# Tello_Power_PCB.net
KiCad netlist of a schematic drawn in EAGLE
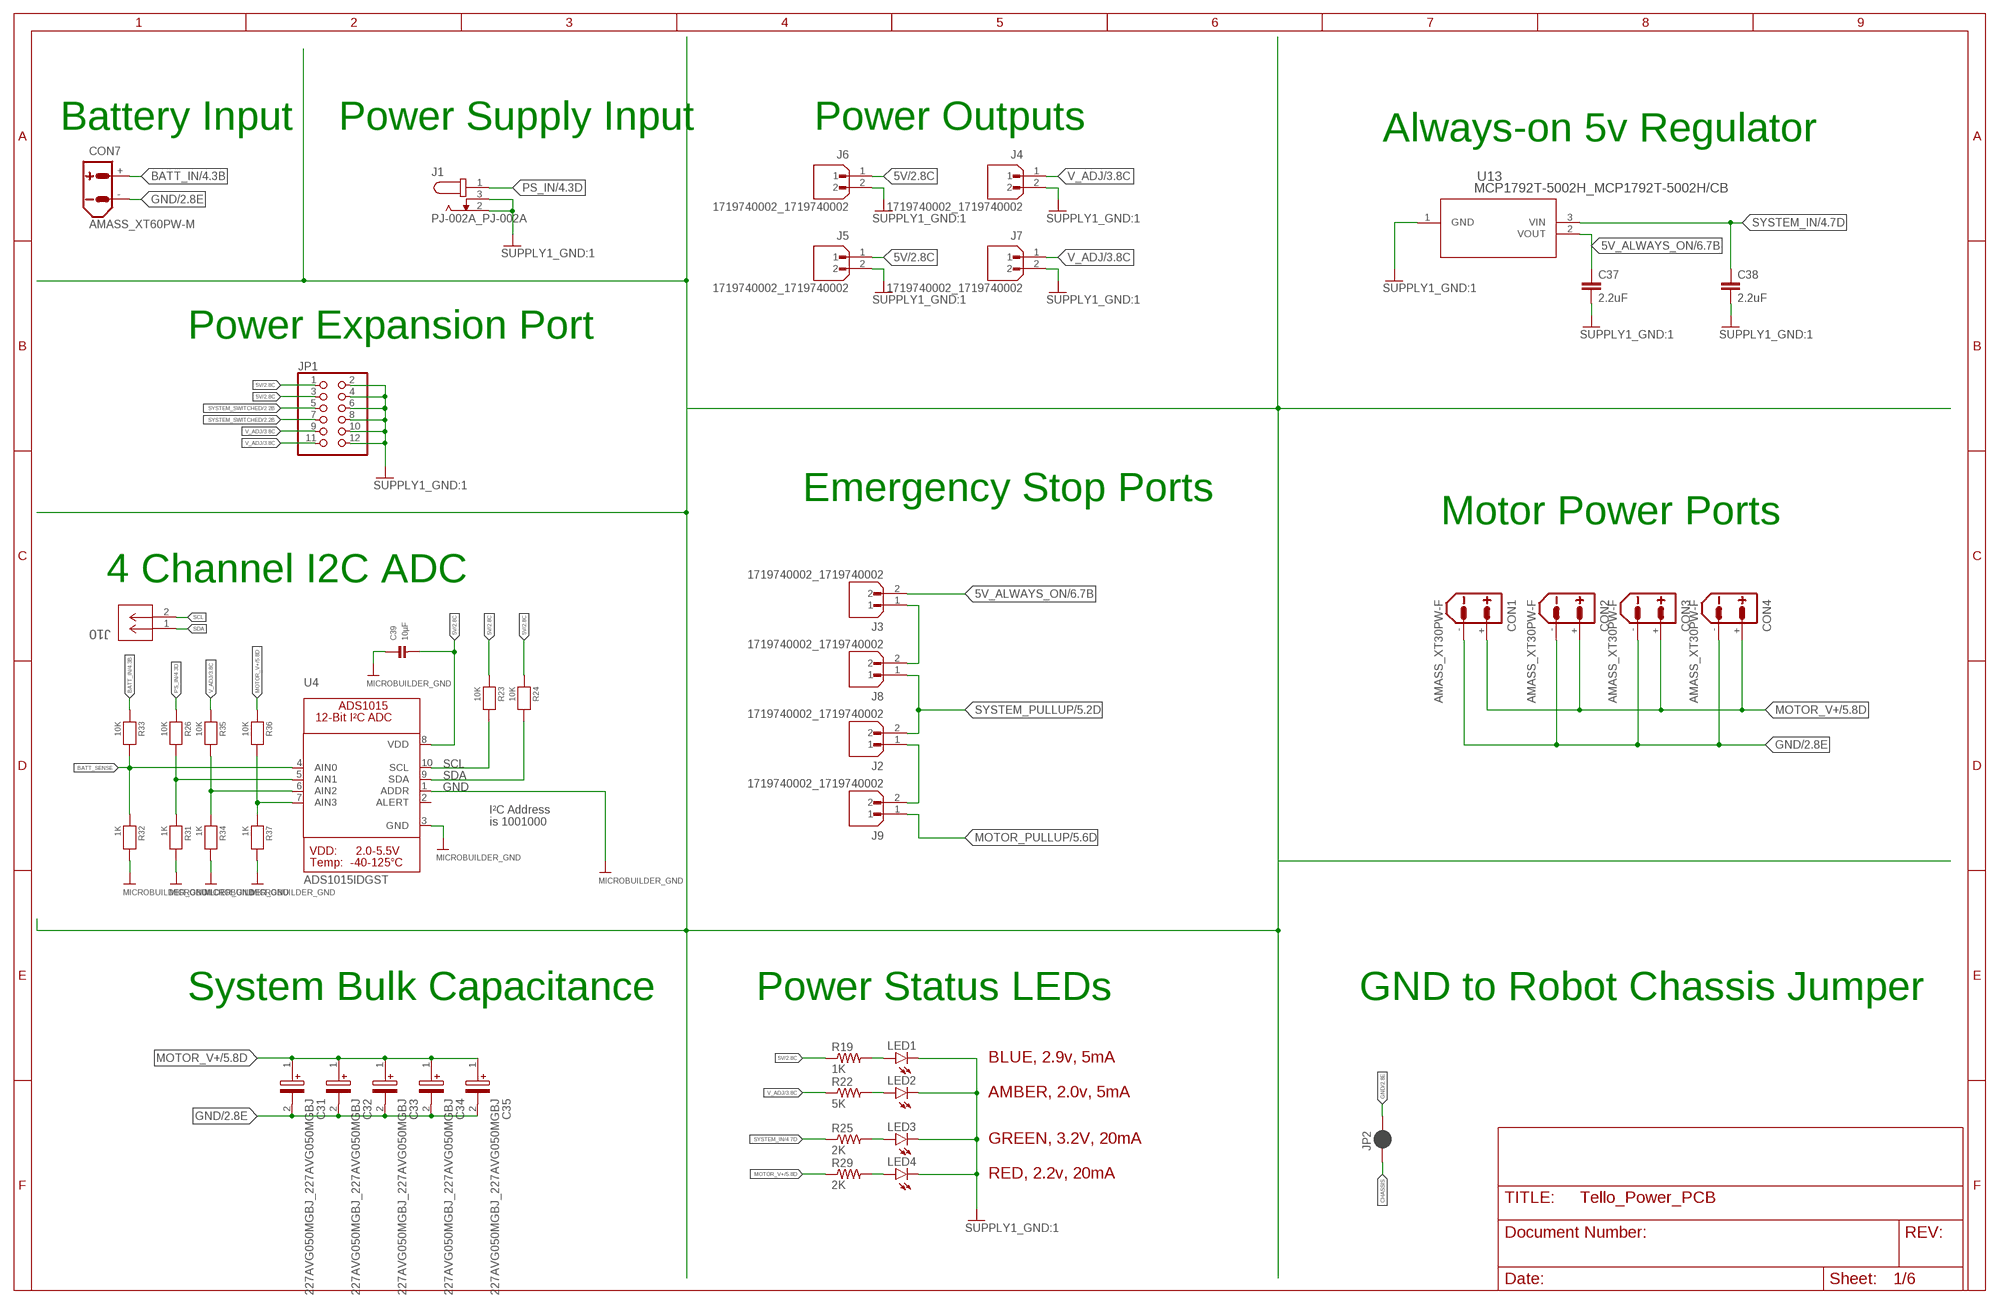
[diagram p0: schematic, sheet 1]
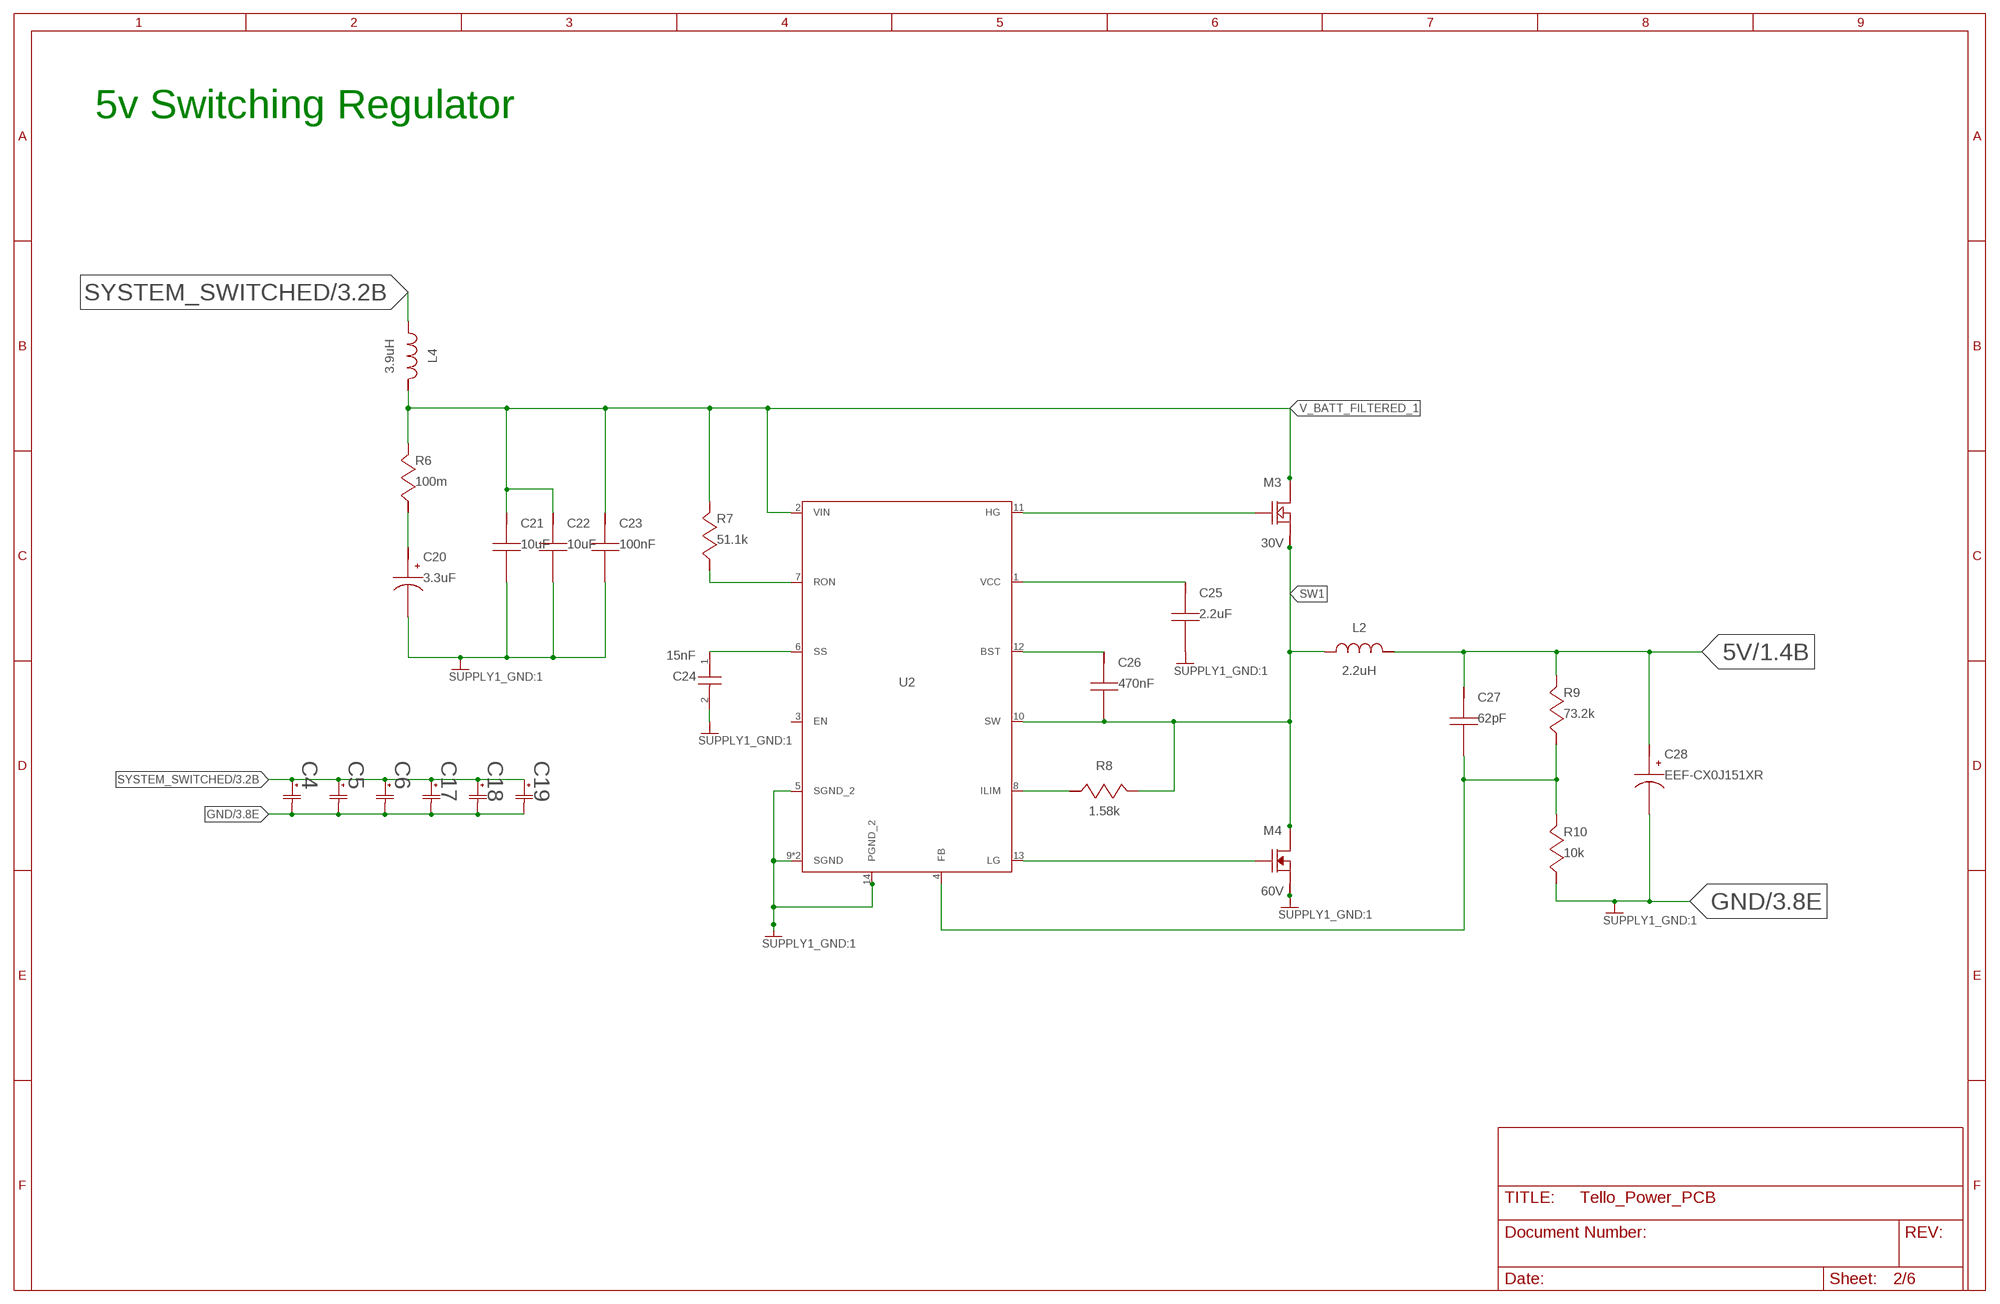
[diagram p1: schematic, sheet 2]
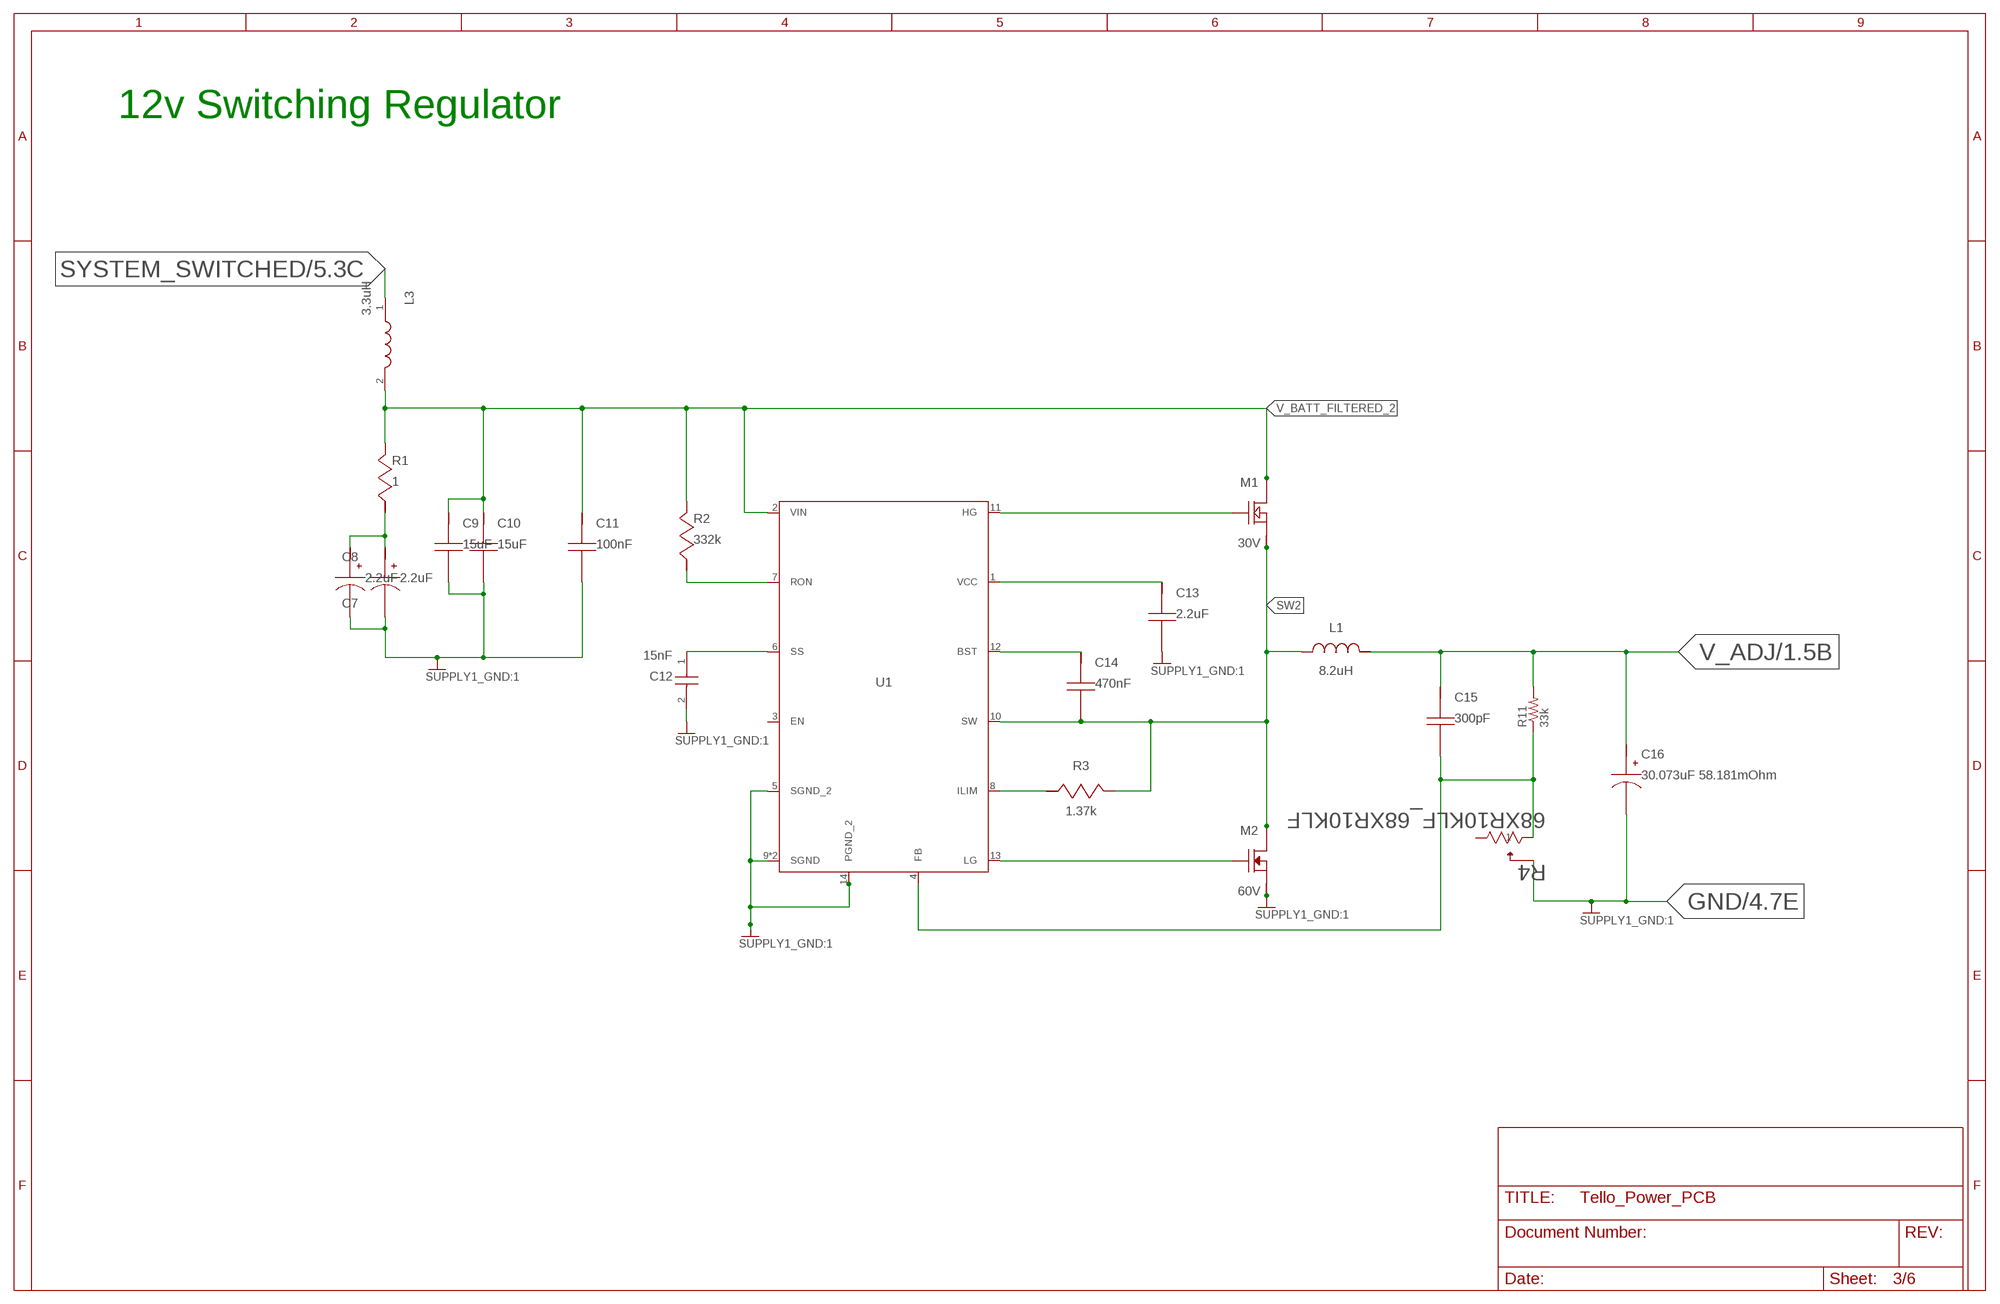
[diagram p2: schematic, sheet 3]
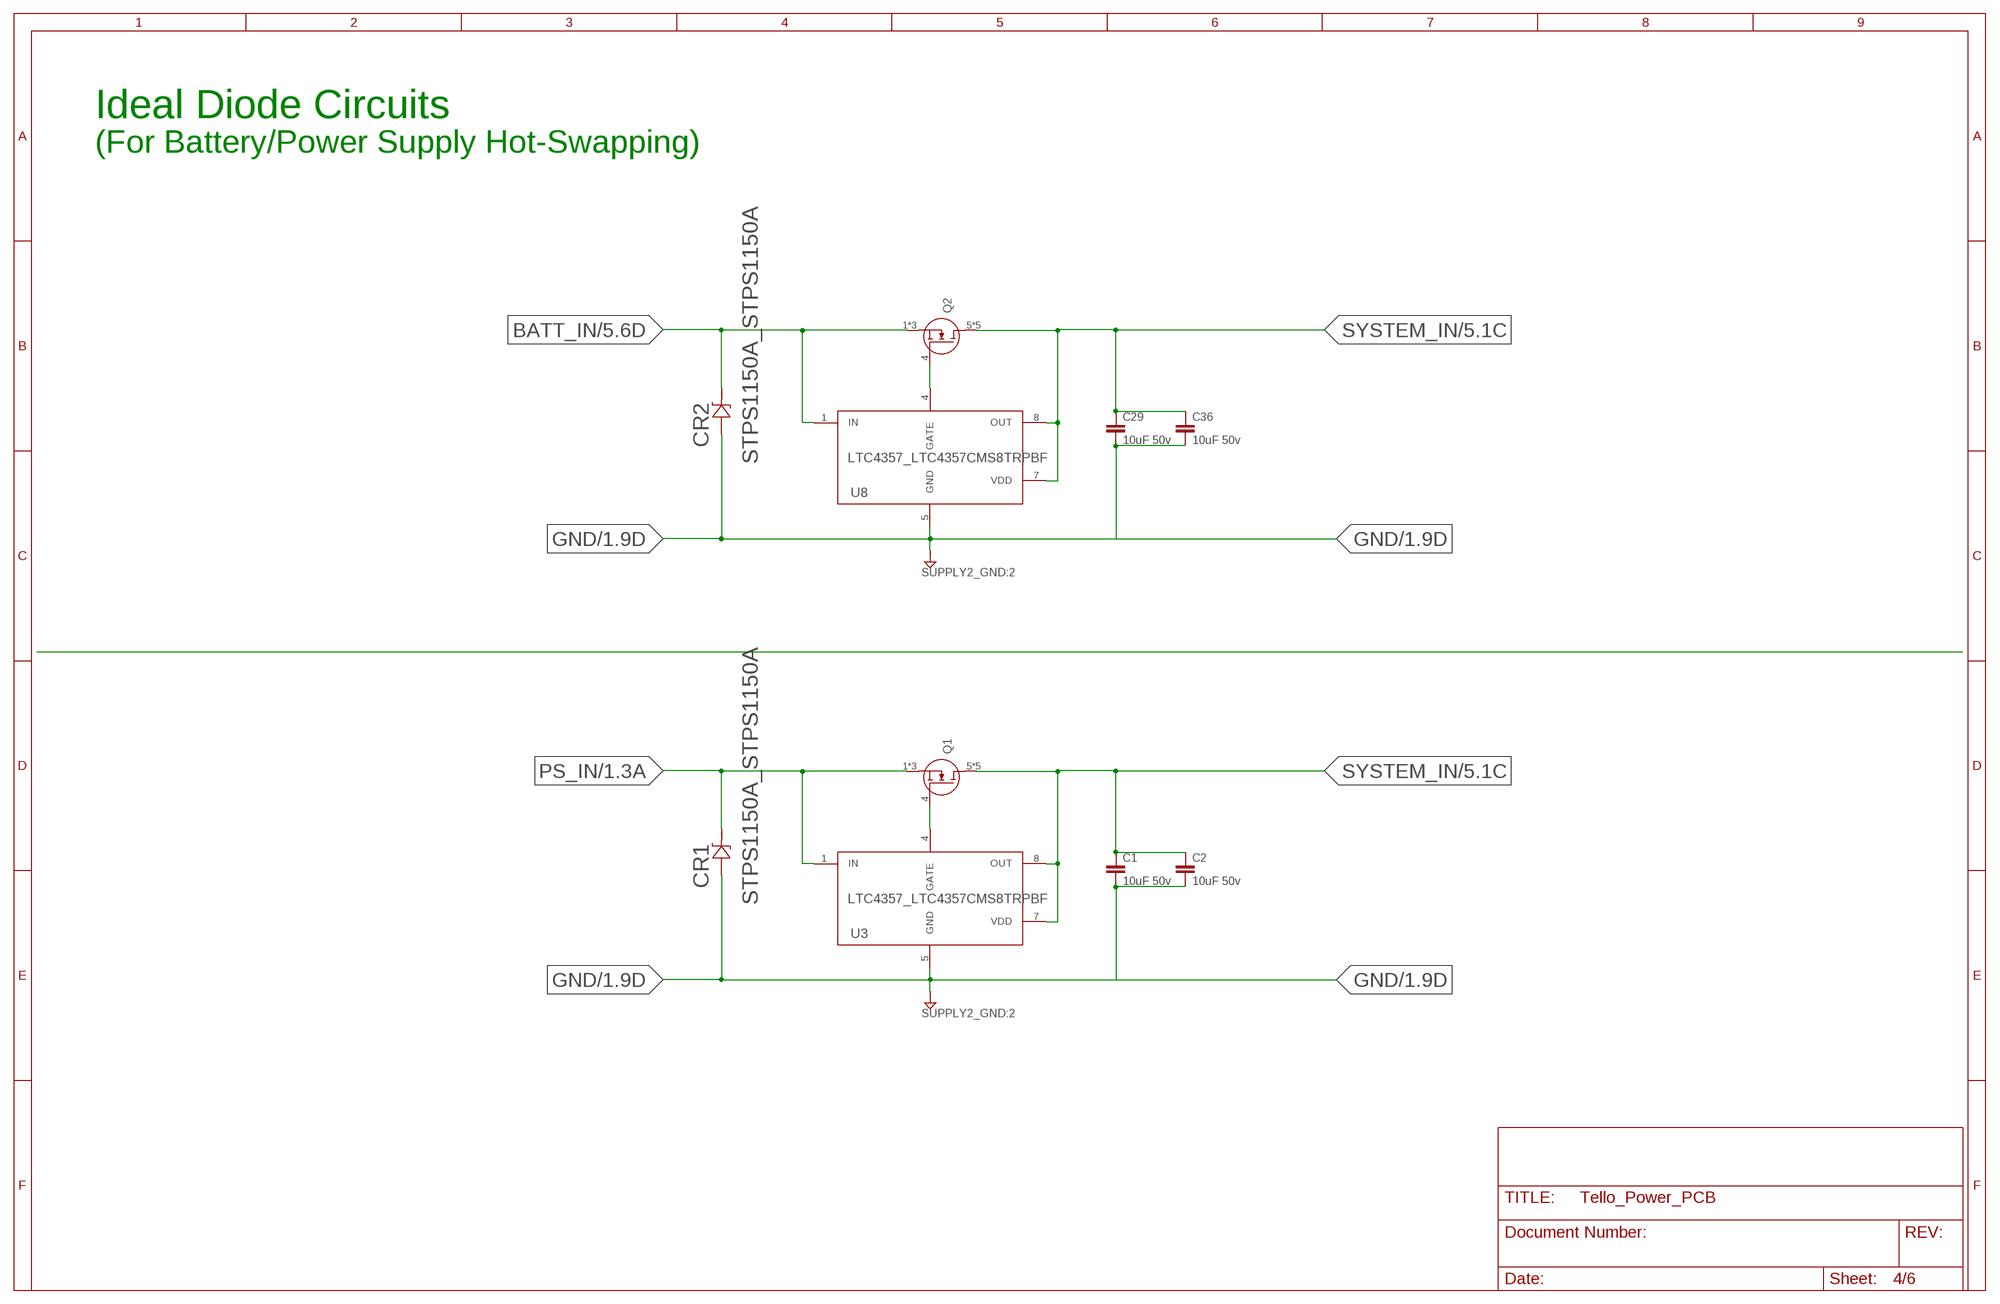
[diagram p3: schematic, sheet 4]
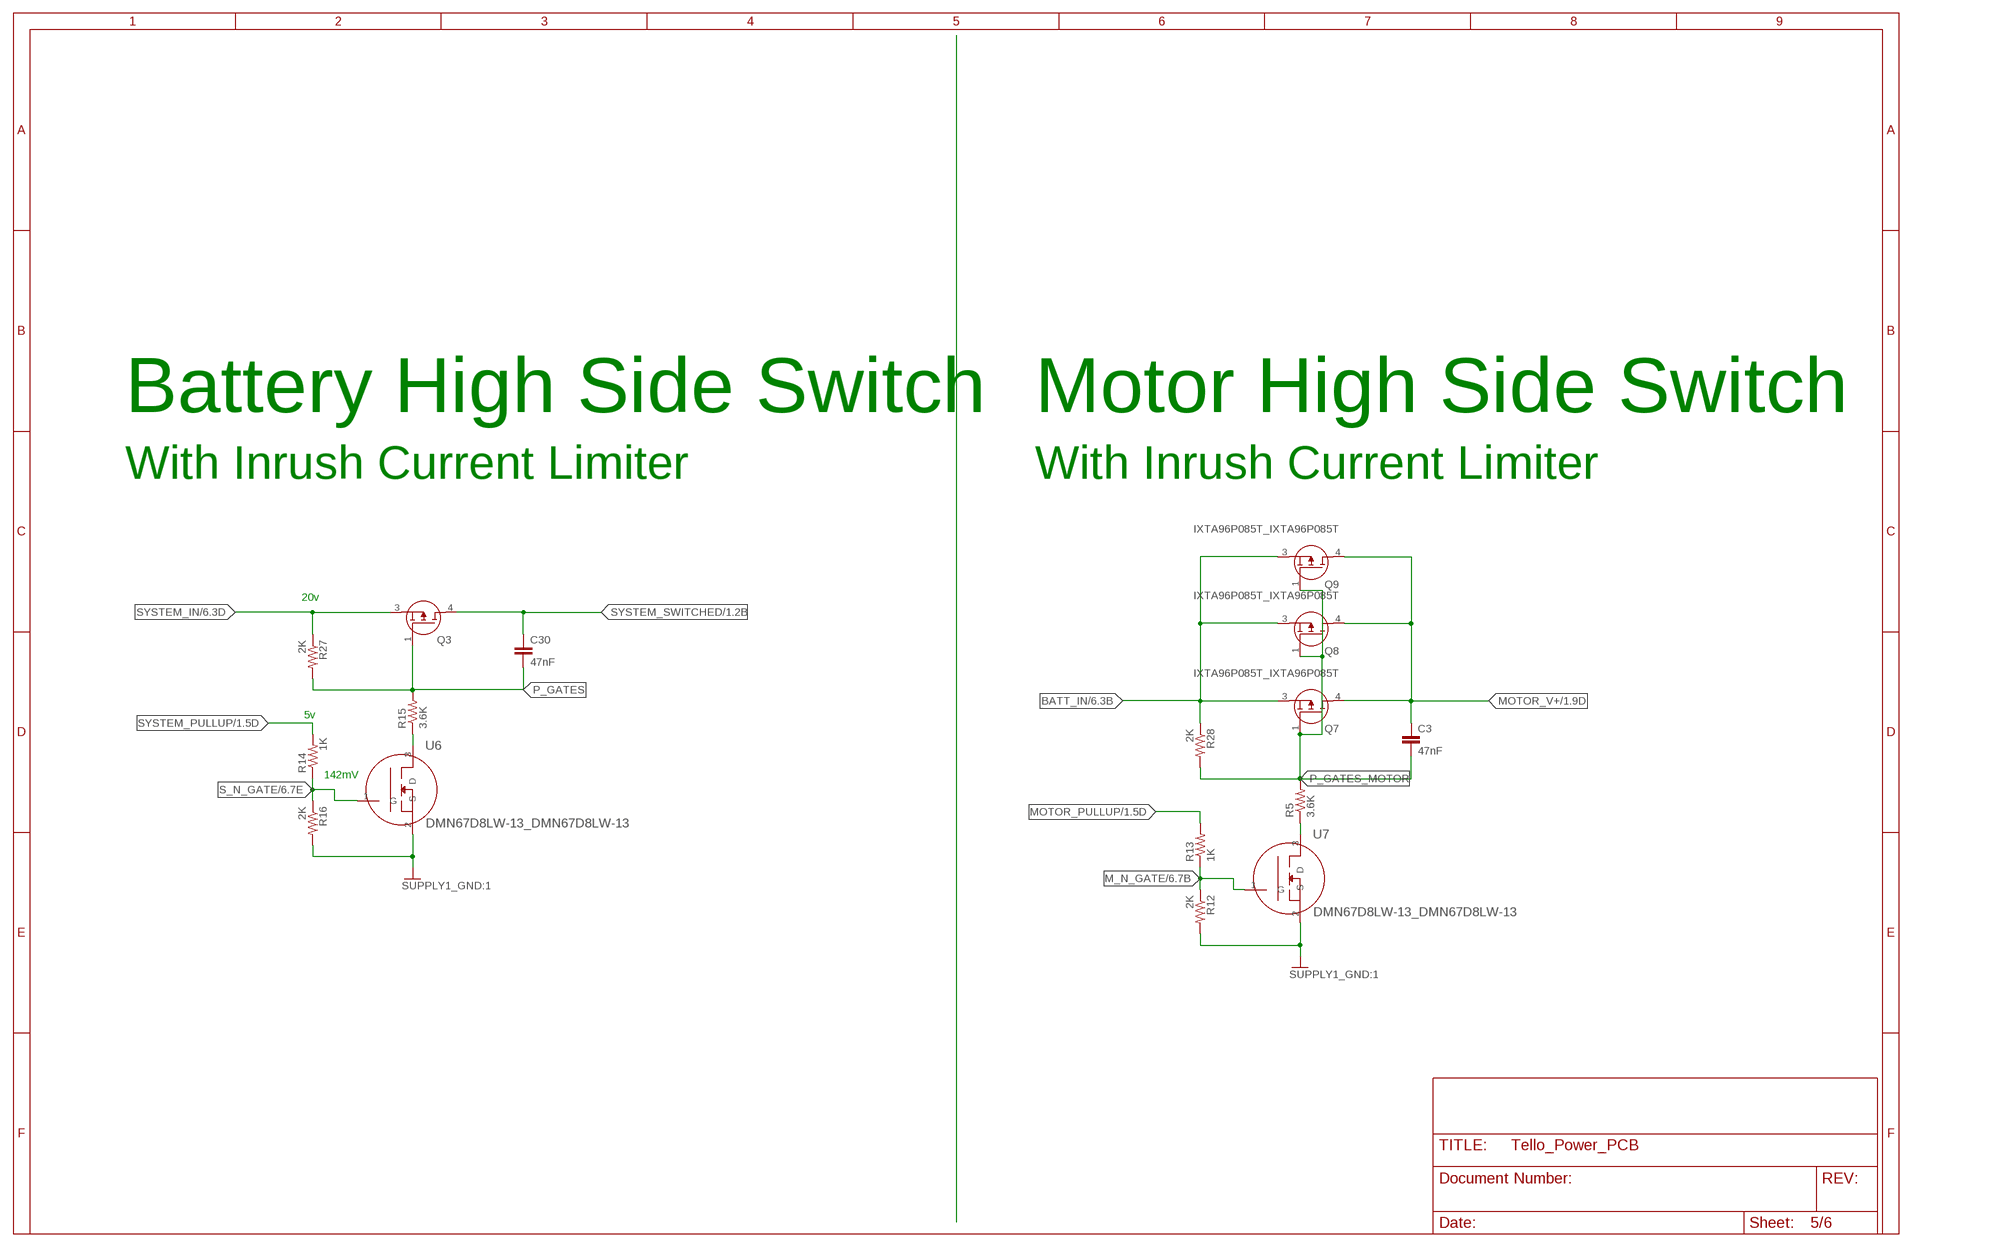
[diagram p4: schematic, sheet 5]
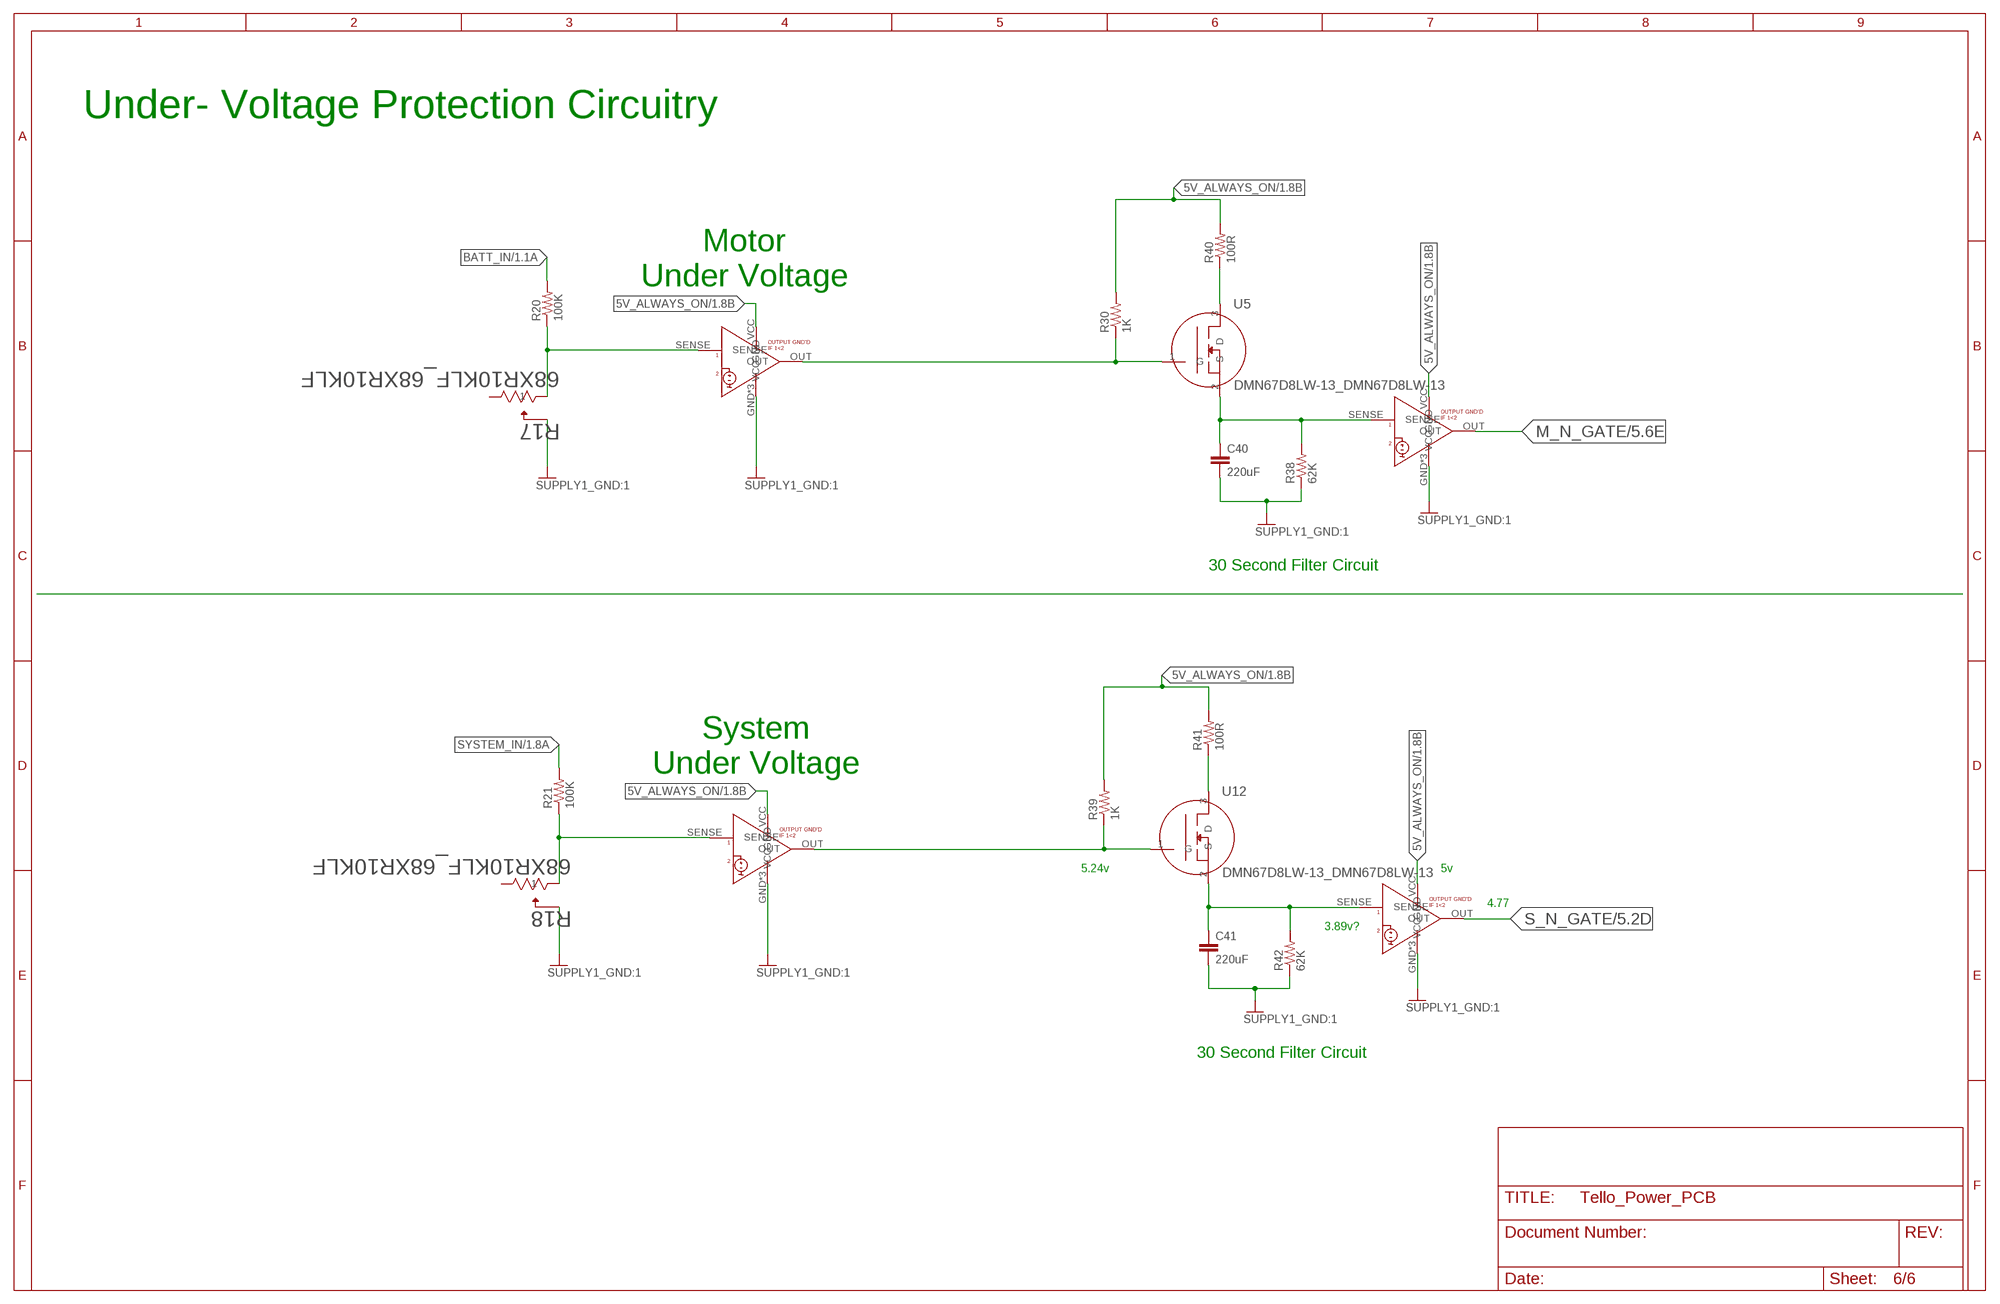
[diagram p5: schematic, sheet 6]

(export (version "E")
  (design (tool "Eeschema 10.0.6"))
  (components
    (comp (ref "C7")
      (value "2.2uF")
      (footprint "eagle-import:12V--LM3150_3528-21")
      (fields (field (name "MANUFACTURER_PART_NUMBER") "TPSB475K035R0700"))
      (libsource (lib "eagle-import") (part "12V--LM3150_TPSB475K035R0700"))
    )
    (comp (ref "C8")
      (value "2.2uF")
      (footprint "eagle-import:12V--LM3150_3528-21")
      (fields (field (name "MANUFACTURER_PART_NUMBER") "TPSB475K035R0700"))
      (libsource (lib "eagle-import") (part "12V--LM3150_TPSB475K035R0700"))
    )
    (comp (ref "C9")
      (value "15uF")
      (footprint "eagle-import:12V--LM3150_0805_1")
      (fields (field (name "MANUFACTURER_PART_NUMBER") "C2012X5R1V156M125AC"))
      (libsource (lib "eagle-import") (part "12V--LM3150_C2012X5R1V156M125AC"))
    )
    (comp (ref "C10")
      (value "15uF")
      (footprint "eagle-import:12V--LM3150_0805_1")
      (fields (field (name "MANUFACTURER_PART_NUMBER") "C2012X5R1V156M125AC"))
      (libsource (lib "eagle-import") (part "12V--LM3150_C2012X5R1V156M125AC"))
    )
    (comp (ref "C11")
      (value "100nF")
      (footprint "eagle-import:12V--LM3150_0402")
      (fields (field (name "MANUFACTURER_PART_NUMBER") "C1005X5R1H104K050BB"))
      (libsource (lib "eagle-import") (part "12V--LM3150_C1005X5R1H104K050BB"))
    )
    (comp (ref "C12")
      (value "15nF")
      (footprint "eagle-import:CGA4F2C0G1H153J085AA_CAPC2012X100N")
      (fields
        (field (name "MANUFACTURER_PART_NUMBER") "CGA4F2C0G1H153J085AA")
        (field (name "MOUSER_PART_NUMBER") "810-CGA4F2C0G1H153J")
        (field (name "RS_PART_NUMBER") "9155168")
      )
      (libsource (lib "eagle-import") (part "CGA4F2C0G1H153J085AA_CGA4F2C0G1H153J085AA"))
    )
    (comp (ref "C13")
      (value "2.2uF")
      (footprint "eagle-import:12V--LM3150_0805_1")
      (fields (field (name "MANUFACTURER_PART_NUMBER") "EMK212BJ225KGT"))
      (libsource (lib "eagle-import") (part "12V--LM3150_EMK212BJ225KG-T?{colon}1"))
    )
    (comp (ref "C14")
      (value "470nF")
      (footprint "eagle-import:12V--LM3150_1206_1")
      (fields (field (name "MANUFACTURER_PART_NUMBER") "ECPU1C474MA5"))
      (libsource (lib "eagle-import") (part "12V--LM3150_ECPU1C474MA5?{colon}1"))
    )
    (comp (ref "C15")
      (value "300pF")
      (footprint "eagle-import:12V--LM3150_0805_1")
      (fields (field (name "MANUFACTURER_PART_NUMBER") "C0805C301J5GACTU"))
      (libsource (lib "eagle-import") (part "12V--LM3150_C0805C301J5GACTU"))
    )
    (comp (ref "C16")
      (value "30.073uF 58.181mOhm")
      (footprint "eagle-import:12V--LM3150_PCV1E330MCL1GS")
      (libsource (lib "eagle-import") (part "12V--LM3150_PCV1E330MCL1GS"))
    )
    (comp (ref "L1")
      (value "8.2uH")
      (footprint "eagle-import:12V--LM3150_WE-LHMI_8040")
      (fields (field (name "MANUFACTURER_PART_NUMBER") "74437358082"))
      (libsource (lib "eagle-import") (part "12V--LM3150_74437358082"))
    )
    (comp (ref "L3")
      (value "3.3uH")
      (footprint "eagle-import:XAL4030-332MEB_XAL4030-332MEB")
      (fields
        (field (name "MANUFACTURER_PART_NUMBER") "XAL4030-332MEB")
        (field (name "MOUSER_PART_NUMBER") "994-XAL4030-332MEB")
      )
      (libsource (lib "eagle-import") (part "XAL4030-332MEB_XAL4030-332MEB"))
    )
    (comp (ref "M1")
      (value "30V")
      (footprint "eagle-import:12V--LM3150_TRANS_NEXFET_Q5A_1")
      (fields (field (name "MANUFACTURER_PART_NUMBER") "CSD17579Q5A"))
      (libsource (lib "eagle-import") (part "12V--LM3150_CSD17579Q5A?{colon}1"))
    )
    (comp (ref "M2")
      (value "60V")
      (footprint "eagle-import:12V--LM3150_TRANS_NEXFET_Q5A_1")
      (fields (field (name "MANUFACTURER_PART_NUMBER") "CSD18537NQ5A"))
      (libsource (lib "eagle-import") (part "12V--LM3150_CSD18537NQ5A?{colon}1"))
    )
    (comp (ref "R1")
      (value "1")
      (footprint "eagle-import:12V--LM3150_0402")
      (fields
        (field (name "MANUFACTURER_PART_NUMBER") "CRCW04021R00FKED")
        (field (name "POWER") "0.063")
        (field (name "TOLERANCE") "1.0")
      )
      (libsource (lib "eagle-import") (part "12V--LM3150_CRCW04021R00FKED"))
    )
    (comp (ref "R2")
      (value "332k")
      (footprint "eagle-import:12V--LM3150_0805_1")
      (fields
        (field (name "MANUFACTURER_PART_NUMBER") "ERJ6ENF3323V")
        (field (name "POWER") "0.125")
        (field (name "TOLERANCE") "1.0")
      )
      (libsource (lib "eagle-import") (part "12V--LM3150_ERJ-6ENF3323V"))
    )
    (comp (ref "R3")
      (value "1.37k")
      (footprint "eagle-import:12V--LM3150_0805_1")
      (fields
        (field (name "MANUFACTURER_PART_NUMBER") "ERJ6ENF1371V")
        (field (name "POWER") "0.125")
        (field (name "TOLERANCE") "1.0")
      )
      (libsource (lib "eagle-import") (part "12V--LM3150_ERJ-6ENF1371V"))
    )
    (comp (ref "R4")
      (value "68XR10KLF_68XR10KLF")
      (footprint "eagle-import:68XR10KLF_RES3_68X_TTE")
      (fields
        (field (name "MANUFACTURER_PART_NUMBER") "68XR10KLF")
        (field (name "COPYRIGHT") "Copyright (C) 2022 Ultra Librarian. All rights reserved.")
      )
      (libsource (lib "eagle-import") (part "68XR10KLF_68XR10KLF"))
    )
    (comp (ref "R11")
      (value "33k")
      (footprint "eagle-import:RCL_R0805")
      (libsource (lib "eagle-import") (part "RCL_R-US_R0805"))
    )
    (comp (ref "U1")
      (value "5V-LM3150MH_LM3150MH/NOPB")
      (footprint "eagle-import:5V-LM3150MH_MXA14A")
      (fields (field (name "MANUFACTURER_PART_NUMBER") "LM3150MHNOPB"))
      (libsource (lib "eagle-import") (part "5V-LM3150MH_LM3150MH/NOPB"))
    )
    (comp (ref "C40")
      (value "220uF")
      (footprint "eagle-import:RCL_C1210")
      (libsource (lib "eagle-import") (part "RCL_C-EUC1210"))
    )
    (comp (ref "C41")
      (value "220uF")
      (footprint "eagle-import:RCL_C1210")
      (libsource (lib "eagle-import") (part "RCL_C-EUC1210"))
    )
    (comp (ref "R17")
      (value "68XR10KLF_68XR10KLF")
      (footprint "eagle-import:68XR10KLF_RES3_68X_TTE")
      (fields
        (field (name "MANUFACTURER_PART_NUMBER") "68XR10KLF")
        (field (name "COPYRIGHT") "Copyright (C) 2022 Ultra Librarian. All rights reserved.")
      )
      (libsource (lib "eagle-import") (part "68XR10KLF_68XR10KLF"))
    )
    (comp (ref "R18")
      (value "68XR10KLF_68XR10KLF")
      (footprint "eagle-import:68XR10KLF_RES3_68X_TTE")
      (fields
        (field (name "MANUFACTURER_PART_NUMBER") "68XR10KLF")
        (field (name "COPYRIGHT") "Copyright (C) 2022 Ultra Librarian. All rights reserved.")
      )
      (libsource (lib "eagle-import") (part "68XR10KLF_68XR10KLF"))
    )
    (comp (ref "R20")
      (value "100K")
      (footprint "eagle-import:RCL_R0603")
      (libsource (lib "eagle-import") (part "RCL_R-US_R0603"))
    )
    (comp (ref "R21")
      (value "100K")
      (footprint "eagle-import:RCL_R0603")
      (libsource (lib "eagle-import") (part "RCL_R-US_R0603"))
    )
    (comp (ref "R30")
      (value "1K")
      (footprint "eagle-import:RCL_R0603")
      (libsource (lib "eagle-import") (part "RCL_R-US_R0603"))
    )
    (comp (ref "R38")
      (value "62K")
      (footprint "eagle-import:RCL_R0603")
      (libsource (lib "eagle-import") (part "RCL_R-US_R0603"))
    )
    (comp (ref "R39")
      (value "1K")
      (footprint "eagle-import:RCL_R0603")
      (libsource (lib "eagle-import") (part "RCL_R-US_R0603"))
    )
    (comp (ref "R40")
      (value "100R")
      (footprint "eagle-import:RCL_R0603")
      (libsource (lib "eagle-import") (part "RCL_R-US_R0603"))
    )
    (comp (ref "R41")
      (value "100R")
      (footprint "eagle-import:RCL_R0603")
      (libsource (lib "eagle-import") (part "RCL_R-US_R0603"))
    )
    (comp (ref "R42")
      (value "62K")
      (footprint "eagle-import:RCL_R0603")
      (libsource (lib "eagle-import") (part "RCL_R-US_R0603"))
    )
    (comp (ref "U5")
      (value "DMN67D8LW-13_DMN67D8LW-13")
      (footprint "eagle-import:DMN67D8LW-13_DMN67D8LW-13_DIO")
      (fields
        (field (name "MANUFACTURER_PART_NUMBER") "DMN67D8LW-13")
        (field (name "COPYRIGHT") "Copyright (C) 2022 Ultra Librarian. All rights reserved.")
      )
      (libsource (lib "eagle-import") (part "DMN67D8LW-13_DMN67D8LW-13"))
    )
    (comp (ref "U9")
      (value "TLV6713DDC_TLV6713DDCTDDC0006A_M")
      (footprint "eagle-import:TLV6713DDC_DDC0006A_M")
      (fields
        (field (name "MANUFACTURER_PART_NUMBER") "TLV6713DDCT")
        (field (name "COPYRIGHT") "Copyright (C) 2022 Ultra Librarian. All rights reserved.")
      )
      (libsource (lib "eagle-import") (part "TLV6713DDC_TLV6713DDCTDDC0006A_M"))
    )
    (comp (ref "U10")
      (value "TLV6713DDC_TLV6713DDCTDDC0006A_M")
      (footprint "eagle-import:TLV6713DDC_DDC0006A_M")
      (fields
        (field (name "MANUFACTURER_PART_NUMBER") "TLV6713DDCT")
        (field (name "COPYRIGHT") "Copyright (C) 2022 Ultra Librarian. All rights reserved.")
      )
      (libsource (lib "eagle-import") (part "TLV6713DDC_TLV6713DDCTDDC0006A_M"))
    )
    (comp (ref "U11")
      (value "TLV6713DDC_TLV6713DDCTDDC0006A_M")
      (footprint "eagle-import:TLV6713DDC_DDC0006A_M")
      (fields
        (field (name "MANUFACTURER_PART_NUMBER") "TLV6713DDCT")
        (field (name "COPYRIGHT") "Copyright (C) 2022 Ultra Librarian. All rights reserved.")
      )
      (libsource (lib "eagle-import") (part "TLV6713DDC_TLV6713DDCTDDC0006A_M"))
    )
    (comp (ref "U12")
      (value "DMN67D8LW-13_DMN67D8LW-13")
      (footprint "eagle-import:DMN67D8LW-13_DMN67D8LW-13_DIO")
      (fields
        (field (name "MANUFACTURER_PART_NUMBER") "DMN67D8LW-13")
        (field (name "COPYRIGHT") "Copyright (C) 2022 Ultra Librarian. All rights reserved.")
      )
      (libsource (lib "eagle-import") (part "DMN67D8LW-13_DMN67D8LW-13"))
    )
    (comp (ref "U14")
      (value "TLV6713DDC_TLV6713DDCTDDC0006A_M")
      (footprint "eagle-import:TLV6713DDC_DDC0006A_M")
      (fields
        (field (name "MANUFACTURER_PART_NUMBER") "TLV6713DDCT")
        (field (name "COPYRIGHT") "Copyright (C) 2022 Ultra Librarian. All rights reserved.")
      )
      (libsource (lib "eagle-import") (part "TLV6713DDC_TLV6713DDCTDDC0006A_M"))
    )
    (comp (ref "C31")
      (value "227AVG050MGBJ_227AVG050MGBJ")
      (footprint "eagle-import:227AVG050MGBJ_CAPPRD500W60D1025H1350")
      (fields
        (field (name "ARROW_PART_NUMBER") "227AVG050MGBJ")
        (field (name "MOUSER_PART_NUMBER") "598-227AVG050MGBJ")
      )
      (libsource (lib "eagle-import") (part "227AVG050MGBJ_227AVG050MGBJ"))
    )
    (comp (ref "C32")
      (value "227AVG050MGBJ_227AVG050MGBJ")
      (footprint "eagle-import:227AVG050MGBJ_CAPPRD500W60D1025H1350")
      (fields
        (field (name "ARROW_PART_NUMBER") "227AVG050MGBJ")
        (field (name "MOUSER_PART_NUMBER") "598-227AVG050MGBJ")
      )
      (libsource (lib "eagle-import") (part "227AVG050MGBJ_227AVG050MGBJ"))
    )
    (comp (ref "C33")
      (value "227AVG050MGBJ_227AVG050MGBJ")
      (footprint "eagle-import:227AVG050MGBJ_CAPPRD500W60D1025H1350")
      (fields
        (field (name "ARROW_PART_NUMBER") "227AVG050MGBJ")
        (field (name "MOUSER_PART_NUMBER") "598-227AVG050MGBJ")
      )
      (libsource (lib "eagle-import") (part "227AVG050MGBJ_227AVG050MGBJ"))
    )
    (comp (ref "C34")
      (value "227AVG050MGBJ_227AVG050MGBJ")
      (footprint "eagle-import:227AVG050MGBJ_CAPPRD500W60D1025H1350")
      (fields
        (field (name "ARROW_PART_NUMBER") "227AVG050MGBJ")
        (field (name "MOUSER_PART_NUMBER") "598-227AVG050MGBJ")
      )
      (libsource (lib "eagle-import") (part "227AVG050MGBJ_227AVG050MGBJ"))
    )
    (comp (ref "C35")
      (value "227AVG050MGBJ_227AVG050MGBJ")
      (footprint "eagle-import:227AVG050MGBJ_CAPPRD500W60D1025H1350")
      (fields
        (field (name "ARROW_PART_NUMBER") "227AVG050MGBJ")
        (field (name "MOUSER_PART_NUMBER") "598-227AVG050MGBJ")
      )
      (libsource (lib "eagle-import") (part "227AVG050MGBJ_227AVG050MGBJ"))
    )
    (comp (ref "C37")
      (value "2.2uF")
      (footprint "eagle-import:RCL_C0603")
      (libsource (lib "eagle-import") (part "RCL_C-EUC0603"))
    )
    (comp (ref "C38")
      (value "2.2uF")
      (footprint "eagle-import:RCL_C1206")
      (libsource (lib "eagle-import") (part "RCL_C-EUC1206"))
    )
    (comp (ref "C39")
      (value "10µF")
      (footprint "eagle-import:MICROBUILDER_0603_1")
      (libsource (lib "eagle-import") (part "MICROBUILDER_CAP_CERAMIC0603"))
    )
    (comp (ref "CON1")
      (value "AMASS_XT30PW-F")
      (footprint "eagle-import:AMASS_XT30PW-F")
      (libsource (lib "eagle-import") (part "AMASS_XT30PW-F"))
    )
    (comp (ref "CON2")
      (value "AMASS_XT30PW-F")
      (footprint "eagle-import:AMASS_XT30PW-F")
      (libsource (lib "eagle-import") (part "AMASS_XT30PW-F"))
    )
    (comp (ref "CON3")
      (value "AMASS_XT30PW-F")
      (footprint "eagle-import:AMASS_XT30PW-F")
      (libsource (lib "eagle-import") (part "AMASS_XT30PW-F"))
    )
    (comp (ref "CON4")
      (value "AMASS_XT30PW-F")
      (footprint "eagle-import:AMASS_XT30PW-F")
      (libsource (lib "eagle-import") (part "AMASS_XT30PW-F"))
    )
    (comp (ref "CON7")
      (value "AMASS_XT60PW-M")
      (footprint "eagle-import:AMASS_XT60PW-M")
      (libsource (lib "eagle-import") (part "AMASS_XT60PW-M"))
    )
    (comp (ref "J1")
      (value "PJ-002A_PJ-002A")
      (footprint "eagle-import:PJ-002A_CUI_PJ-002A")
      (fields
        (field (name "DIGI-KEY_PART_NUMBER") "CP-002A-ND")
        (field (name "MF") "CUI Devices")
        (field (name "MP") "PJ-002A")
      )
      (libsource (lib "eagle-import") (part "PJ-002A_PJ-002A"))
    )
    (comp (ref "J2")
      (value "1719740002_1719740002")
      (footprint "eagle-import:1719740002_MOLEX_1719740002")
      (fields
        (field (name "DIGI-KEY_PART_NUMBER") "WM22662-ND")
        (field (name "MF") "Molex")
        (field (name "MP") "1719740002")
      )
      (libsource (lib "eagle-import") (part "1719740002_1719740002"))
    )
    (comp (ref "J3")
      (value "1719740002_1719740002")
      (footprint "eagle-import:1719740002_MOLEX_1719740002")
      (fields
        (field (name "DIGI-KEY_PART_NUMBER") "WM22662-ND")
        (field (name "MF") "Molex")
        (field (name "MP") "1719740002")
      )
      (libsource (lib "eagle-import") (part "1719740002_1719740002"))
    )
    (comp (ref "J4")
      (value "1719740002_1719740002")
      (footprint "eagle-import:1719740002_MOLEX_1719740002")
      (fields
        (field (name "DIGI-KEY_PART_NUMBER") "WM22662-ND")
        (field (name "MF") "Molex")
        (field (name "MP") "1719740002")
      )
      (libsource (lib "eagle-import") (part "1719740002_1719740002"))
    )
    (comp (ref "J5")
      (value "1719740002_1719740002")
      (footprint "eagle-import:1719740002_MOLEX_1719740002")
      (fields
        (field (name "DIGI-KEY_PART_NUMBER") "WM22662-ND")
        (field (name "MF") "Molex")
        (field (name "MP") "1719740002")
      )
      (libsource (lib "eagle-import") (part "1719740002_1719740002"))
    )
    (comp (ref "J6")
      (value "1719740002_1719740002")
      (footprint "eagle-import:1719740002_MOLEX_1719740002")
      (fields
        (field (name "DIGI-KEY_PART_NUMBER") "WM22662-ND")
        (field (name "MF") "Molex")
        (field (name "MP") "1719740002")
      )
      (libsource (lib "eagle-import") (part "1719740002_1719740002"))
    )
    (comp (ref "J7")
      (value "1719740002_1719740002")
      (footprint "eagle-import:1719740002_MOLEX_1719740002")
      (fields
        (field (name "DIGI-KEY_PART_NUMBER") "WM22662-ND")
        (field (name "MF") "Molex")
        (field (name "MP") "1719740002")
      )
      (libsource (lib "eagle-import") (part "1719740002_1719740002"))
    )
    (comp (ref "J8")
      (value "1719740002_1719740002")
      (footprint "eagle-import:1719740002_MOLEX_1719740002")
      (fields
        (field (name "DIGI-KEY_PART_NUMBER") "WM22662-ND")
        (field (name "MF") "Molex")
        (field (name "MP") "1719740002")
      )
      (libsource (lib "eagle-import") (part "1719740002_1719740002"))
    )
    (comp (ref "J9")
      (value "1719740002_1719740002")
      (footprint "eagle-import:1719740002_MOLEX_1719740002")
      (fields
        (field (name "DIGI-KEY_PART_NUMBER") "WM22662-ND")
        (field (name "MF") "Molex")
        (field (name "MP") "1719740002")
      )
      (libsource (lib "eagle-import") (part "1719740002_1719740002"))
    )
    (comp (ref "J10")
      (value "SM02B-GHS-TB_SM02BGHSTBLFSN")
      (footprint "eagle-import:SM02B-GHS-TB_CONN_SM02BGHSTB_JST")
      (fields
        (field (name "MANUFACTURER_PART_NUMBER") "SM02BGHSTBLFSN")
        (field (name "COPYRIGHT") "Copyright (C) 2022 Ultra Librarian. All rights reserved.")
      )
      (libsource (lib "eagle-import") (part "SM02B-GHS-TB_SM02BGHSTBLFSN"))
    )
    (comp (ref "JP1")
      (value "PINHEAD_PINHD-2X6")
      (footprint "eagle-import:PINHEAD_2X06")
      (libsource (lib "eagle-import") (part "PINHEAD_PINHD-2X6"))
    )
    (comp (ref "JP2")
      (value "SPARKFUN-JUMPERS_JUMPER-SMT_2_NC_PASTE_NO-SILK")
      (footprint "eagle-import:SPARKFUN-JUMPERS_SMT-JUMPER_2_NC_PASTE_NO-SILK")
      (libsource (lib "eagle-import") (part "SPARKFUN-JUMPERS_JUMPER-SMT_2_NC_PASTE_NO-SILK"))
    )
    (comp (ref "LED1")
      (value "LED_LEDCHIP-LED0603")
      (footprint "eagle-import:LED_CHIP-LED0603")
      (libsource (lib "eagle-import") (part "LED_LEDCHIP-LED0603"))
    )
    (comp (ref "LED2")
      (value "LED_LEDCHIP-LED0603")
      (footprint "eagle-import:LED_CHIP-LED0603")
      (libsource (lib "eagle-import") (part "LED_LEDCHIP-LED0603"))
    )
    (comp (ref "LED3")
      (value "LED_LEDCHIP-LED0603")
      (footprint "eagle-import:LED_CHIP-LED0603")
      (libsource (lib "eagle-import") (part "LED_LEDCHIP-LED0603"))
    )
    (comp (ref "LED4")
      (value "LED_LEDCHIP-LED0603")
      (footprint "eagle-import:LED_CHIP-LED0603")
      (libsource (lib "eagle-import") (part "LED_LEDCHIP-LED0603"))
    )
    (comp (ref "R19")
      (value "1K")
      (footprint "eagle-import:RCL_R0603")
      (libsource (lib "eagle-import") (part "RCL_R-US_R0603"))
    )
    (comp (ref "R22")
      (value "5K")
      (footprint "eagle-import:RCL_R0603")
      (libsource (lib "eagle-import") (part "RCL_R-US_R0603"))
    )
    (comp (ref "R23")
      (value "10K")
      (footprint "eagle-import:MICROBUILDER_0603_1")
      (libsource (lib "eagle-import") (part "MICROBUILDER_RESISTOR0603"))
    )
    (comp (ref "R24")
      (value "10K")
      (footprint "eagle-import:MICROBUILDER_0603_1")
      (libsource (lib "eagle-import") (part "MICROBUILDER_RESISTOR0603"))
    )
    (comp (ref "R25")
      (value "2K")
      (footprint "eagle-import:RCL_R0603")
      (libsource (lib "eagle-import") (part "RCL_R-US_R0603"))
    )
    (comp (ref "R26")
      (value "10K")
      (footprint "eagle-import:MICROBUILDER_0603_1")
      (libsource (lib "eagle-import") (part "MICROBUILDER_RESISTOR0603"))
    )
    (comp (ref "R29")
      (value "2K")
      (footprint "eagle-import:RCL_R0603")
      (libsource (lib "eagle-import") (part "RCL_R-US_R0603"))
    )
    (comp (ref "R31")
      (value "1K")
      (footprint "eagle-import:MICROBUILDER_0603_1")
      (libsource (lib "eagle-import") (part "MICROBUILDER_RESISTOR0603"))
    )
    (comp (ref "R32")
      (value "1K")
      (footprint "eagle-import:MICROBUILDER_0603_1")
      (libsource (lib "eagle-import") (part "MICROBUILDER_RESISTOR0603"))
    )
    (comp (ref "R33")
      (value "10K")
      (footprint "eagle-import:MICROBUILDER_0603_1")
      (libsource (lib "eagle-import") (part "MICROBUILDER_RESISTOR0603"))
    )
    (comp (ref "R34")
      (value "1K")
      (footprint "eagle-import:MICROBUILDER_0603_1")
      (libsource (lib "eagle-import") (part "MICROBUILDER_RESISTOR0603"))
    )
    (comp (ref "R35")
      (value "10K")
      (footprint "eagle-import:MICROBUILDER_0603_1")
      (libsource (lib "eagle-import") (part "MICROBUILDER_RESISTOR0603"))
    )
    (comp (ref "R36")
      (value "10K")
      (footprint "eagle-import:MICROBUILDER_0603_1")
      (libsource (lib "eagle-import") (part "MICROBUILDER_RESISTOR0603"))
    )
    (comp (ref "R37")
      (value "1K")
      (footprint "eagle-import:MICROBUILDER_0603_1")
      (libsource (lib "eagle-import") (part "MICROBUILDER_RESISTOR0603"))
    )
    (comp (ref "U4")
      (value "ADS1015IDGST")
      (footprint "eagle-import:MICROBUILDER_MSOP10")
      (libsource (lib "eagle-import") (part "MICROBUILDER_ADC_ADS1015"))
    )
    (comp (ref "U13")
      (value "MCP1792T-5002H_MCP1792T-5002H/CB")
      (footprint "eagle-import:MCP1792T-5002H_SOT-23A_CB_MCH")
      (fields
        (field (name "MANUFACTURER_PART_NUMBER") "MCP1792T-5002H/CB")
        (field (name "COPYRIGHT") "Copyright (C) 2022 Ultra Librarian. All rights reserved.")
      )
      (libsource (lib "eagle-import") (part "MCP1792T-5002H_MCP1792T-5002H/CB"))
    )
    (comp (ref "C1")
      (value "10uF 50v")
      (footprint "eagle-import:RCL_C1206")
      (libsource (lib "eagle-import") (part "RCL_C-EUC1206"))
    )
    (comp (ref "C2")
      (value "10uF 50v")
      (footprint "eagle-import:RCL_C1206")
      (libsource (lib "eagle-import") (part "RCL_C-EUC1206"))
    )
    (comp (ref "C29")
      (value "10uF 50v")
      (footprint "eagle-import:RCL_C1206")
      (libsource (lib "eagle-import") (part "RCL_C-EUC1206"))
    )
    (comp (ref "C36")
      (value "10uF 50v")
      (footprint "eagle-import:RCL_C1206")
      (libsource (lib "eagle-import") (part "RCL_C-EUC1206"))
    )
    (comp (ref "CR1")
      (value "STPS1150A_STPS1150A")
      (footprint "eagle-import:STPS1150A_SMA_STM")
      (fields (field (name "MANUFACTURER_PART_NUMBER") "STPS1150A"))
      (libsource (lib "eagle-import") (part "STPS1150A_STPS1150A"))
    )
    (comp (ref "CR2")
      (value "STPS1150A_STPS1150A")
      (footprint "eagle-import:STPS1150A_SMA_STM")
      (fields (field (name "MANUFACTURER_PART_NUMBER") "STPS1150A"))
      (libsource (lib "eagle-import") (part "STPS1150A_STPS1150A"))
    )
    (comp (ref "Q1")
      (value "BSC027N06LS5ATMA1_BSC027N06LS5ATMA1")
      (footprint "eagle-import:BSC027N06LS5ATMA1_BSC027N06LS5ATMA1")
      (fields
        (field (name "ARROW_PART_NUMBER") "BSC027N06LS5ATMA1")
        (field (name "MOUSER_PART_NUMBER") "726-BSC027N06LS5ATMA")
      )
      (libsource (lib "eagle-import") (part "BSC027N06LS5ATMA1_BSC027N06LS5ATMA1"))
    )
    (comp (ref "Q2")
      (value "BSC027N06LS5ATMA1_BSC027N06LS5ATMA1")
      (footprint "eagle-import:BSC027N06LS5ATMA1_BSC027N06LS5ATMA1")
      (fields
        (field (name "ARROW_PART_NUMBER") "BSC027N06LS5ATMA1")
        (field (name "MOUSER_PART_NUMBER") "726-BSC027N06LS5ATMA")
      )
      (libsource (lib "eagle-import") (part "BSC027N06LS5ATMA1_BSC027N06LS5ATMA1"))
    )
    (comp (ref "U3")
      (value "LTC4357_LTC4357CMS8TRPBF")
      (footprint "eagle-import:LTC4357_MSOP-8_MS_LIT")
      (fields (field (name "MANUFACTURER_PART_NUMBER") "ltc4357cms8#trpbf"))
      (libsource (lib "eagle-import") (part "LTC4357_LTC4357CMS8TRPBF"))
    )
    (comp (ref "U8")
      (value "LTC4357_LTC4357CMS8TRPBF")
      (footprint "eagle-import:LTC4357_MSOP-8_MS_LIT")
      (fields (field (name "MANUFACTURER_PART_NUMBER") "ltc4357cms8#trpbf"))
      (libsource (lib "eagle-import") (part "LTC4357_LTC4357CMS8TRPBF"))
    )
    (comp (ref "C3")
      (value "47nF")
      (footprint "eagle-import:RCL_C0603")
      (libsource (lib "eagle-import") (part "RCL_C-EUC0603"))
    )
    (comp (ref "C30")
      (value "47nF")
      (footprint "eagle-import:RCL_C0603")
      (libsource (lib "eagle-import") (part "RCL_C-EUC0603"))
    )
    (comp (ref "Q3")
      (value "IXTA96P085T_IXTA96P085T")
      (footprint "eagle-import:IXTA96P085T_IXTA96P085T")
      (fields
        (field (name "ARROW_PART_NUMBER") "IXTA96P085T")
        (field (name "MOUSER_PART_NUMBER") "747-IXTA96P085T")
      )
      (libsource (lib "eagle-import") (part "IXTA96P085T_IXTA96P085T"))
    )
    (comp (ref "Q7")
      (value "IXTA96P085T_IXTA96P085T")
      (footprint "eagle-import:IXTA96P085T_IXTA96P085T")
      (fields
        (field (name "ARROW_PART_NUMBER") "IXTA96P085T")
        (field (name "MOUSER_PART_NUMBER") "747-IXTA96P085T")
      )
      (libsource (lib "eagle-import") (part "IXTA96P085T_IXTA96P085T"))
    )
    (comp (ref "Q8")
      (value "IXTA96P085T_IXTA96P085T")
      (footprint "eagle-import:IXTA96P085T_IXTA96P085T")
      (fields
        (field (name "ARROW_PART_NUMBER") "IXTA96P085T")
        (field (name "MOUSER_PART_NUMBER") "747-IXTA96P085T")
      )
      (libsource (lib "eagle-import") (part "IXTA96P085T_IXTA96P085T"))
    )
    (comp (ref "Q9")
      (value "IXTA96P085T_IXTA96P085T")
      (footprint "eagle-import:IXTA96P085T_IXTA96P085T")
      (fields
        (field (name "ARROW_PART_NUMBER") "IXTA96P085T")
        (field (name "MOUSER_PART_NUMBER") "747-IXTA96P085T")
      )
      (libsource (lib "eagle-import") (part "IXTA96P085T_IXTA96P085T"))
    )
    (comp (ref "R5")
      (value "3.6K")
      (footprint "eagle-import:RCL_R0603")
      (libsource (lib "eagle-import") (part "RCL_R-US_R0603"))
    )
    (comp (ref "R12")
      (value "2K")
      (footprint "eagle-import:RCL_R0603")
      (libsource (lib "eagle-import") (part "RCL_R-US_R0603"))
    )
    (comp (ref "R13")
      (value "1K")
      (footprint "eagle-import:RCL_R0603")
      (libsource (lib "eagle-import") (part "RCL_R-US_R0603"))
    )
    (comp (ref "R14")
      (value "1K")
      (footprint "eagle-import:RCL_R0603")
      (libsource (lib "eagle-import") (part "RCL_R-US_R0603"))
    )
    (comp (ref "R15")
      (value "3.6K")
      (footprint "eagle-import:RCL_R0603")
      (libsource (lib "eagle-import") (part "RCL_R-US_R0603"))
    )
    (comp (ref "R16")
      (value "2K")
      (footprint "eagle-import:RCL_R0603")
      (libsource (lib "eagle-import") (part "RCL_R-US_R0603"))
    )
    (comp (ref "R27")
      (value "2K")
      (footprint "eagle-import:RCL_R0603")
      (libsource (lib "eagle-import") (part "RCL_R-US_R0603"))
    )
    (comp (ref "R28")
      (value "2K")
      (footprint "eagle-import:RCL_R0603")
      (libsource (lib "eagle-import") (part "RCL_R-US_R0603"))
    )
    (comp (ref "U6")
      (value "DMN67D8LW-13_DMN67D8LW-13")
      (footprint "eagle-import:DMN67D8LW-13_DMN67D8LW-13_DIO")
      (fields
        (field (name "MANUFACTURER_PART_NUMBER") "DMN67D8LW-13")
        (field (name "COPYRIGHT") "Copyright (C) 2022 Ultra Librarian. All rights reserved.")
      )
      (libsource (lib "eagle-import") (part "DMN67D8LW-13_DMN67D8LW-13"))
    )
    (comp (ref "U7")
      (value "DMN67D8LW-13_DMN67D8LW-13")
      (footprint "eagle-import:DMN67D8LW-13_DMN67D8LW-13_DIO")
      (fields
        (field (name "MANUFACTURER_PART_NUMBER") "DMN67D8LW-13")
        (field (name "COPYRIGHT") "Copyright (C) 2022 Ultra Librarian. All rights reserved.")
      )
      (libsource (lib "eagle-import") (part "DMN67D8LW-13_DMN67D8LW-13"))
    )
    (comp (ref "C4")
      (value "PCR1H820MCL1GS_PCR1H820MCL1GS")
      (footprint "eagle-import:PCR1H820MCL1GS_CAP_PC_10X8_NCH")
      (fields
        (field (name "MANUFACTURER_PART_NUMBER") "PCR1H820MCL1GS")
        (field (name "COPYRIGHT") "Copyright (C) 2022 Ultra Librarian. All rights reserved.")
      )
      (libsource (lib "eagle-import") (part "PCR1H820MCL1GS_PCR1H820MCL1GS"))
    )
    (comp (ref "C5")
      (value "PCR1H820MCL1GS_PCR1H820MCL1GS")
      (footprint "eagle-import:PCR1H820MCL1GS_CAP_PC_10X8_NCH")
      (fields
        (field (name "MANUFACTURER_PART_NUMBER") "PCR1H820MCL1GS")
        (field (name "COPYRIGHT") "Copyright (C) 2022 Ultra Librarian. All rights reserved.")
      )
      (libsource (lib "eagle-import") (part "PCR1H820MCL1GS_PCR1H820MCL1GS"))
    )
    (comp (ref "C6")
      (value "PCR1H820MCL1GS_PCR1H820MCL1GS")
      (footprint "eagle-import:PCR1H820MCL1GS_CAP_PC_10X8_NCH")
      (fields
        (field (name "MANUFACTURER_PART_NUMBER") "PCR1H820MCL1GS")
        (field (name "COPYRIGHT") "Copyright (C) 2022 Ultra Librarian. All rights reserved.")
      )
      (libsource (lib "eagle-import") (part "PCR1H820MCL1GS_PCR1H820MCL1GS"))
    )
    (comp (ref "C17")
      (value "PCR1H820MCL1GS_PCR1H820MCL1GS")
      (footprint "eagle-import:PCR1H820MCL1GS_CAP_PC_10X8_NCH")
      (fields
        (field (name "MANUFACTURER_PART_NUMBER") "PCR1H820MCL1GS")
        (field (name "COPYRIGHT") "Copyright (C) 2022 Ultra Librarian. All rights reserved.")
      )
      (libsource (lib "eagle-import") (part "PCR1H820MCL1GS_PCR1H820MCL1GS"))
    )
    (comp (ref "C18")
      (value "PCR1H820MCL1GS_PCR1H820MCL1GS")
      (footprint "eagle-import:PCR1H820MCL1GS_CAP_PC_10X8_NCH")
      (fields
        (field (name "MANUFACTURER_PART_NUMBER") "PCR1H820MCL1GS")
        (field (name "COPYRIGHT") "Copyright (C) 2022 Ultra Librarian. All rights reserved.")
      )
      (libsource (lib "eagle-import") (part "PCR1H820MCL1GS_PCR1H820MCL1GS"))
    )
    (comp (ref "C19")
      (value "PCR1H820MCL1GS_PCR1H820MCL1GS")
      (footprint "eagle-import:PCR1H820MCL1GS_CAP_PC_10X8_NCH")
      (fields
        (field (name "MANUFACTURER_PART_NUMBER") "PCR1H820MCL1GS")
        (field (name "COPYRIGHT") "Copyright (C) 2022 Ultra Librarian. All rights reserved.")
      )
      (libsource (lib "eagle-import") (part "PCR1H820MCL1GS_PCR1H820MCL1GS"))
    )
    (comp (ref "C20")
      (value "3.3uF")
      (footprint "eagle-import:5V-LM3150MH_6032-28")
      (fields (field (name "MANUFACTURER_PART_NUMBER") "293D335X9035C2TE3"))
      (libsource (lib "eagle-import") (part "5V-LM3150MH_293D335X9035C2TE3"))
    )
    (comp (ref "C21")
      (value "10uF")
      (footprint "eagle-import:5V-LM3150MH_0805")
      (fields (field (name "MANUFACTURER_PART_NUMBER") "C2012X5R1V106K085AC"))
      (libsource (lib "eagle-import") (part "5V-LM3150MH_C2012X5R1V106K085AC"))
    )
    (comp (ref "C22")
      (value "10uF")
      (footprint "eagle-import:5V-LM3150MH_0805")
      (fields (field (name "MANUFACTURER_PART_NUMBER") "C2012X5R1V106K085AC"))
      (libsource (lib "eagle-import") (part "5V-LM3150MH_C2012X5R1V106K085AC"))
    )
    (comp (ref "C23")
      (value "100nF")
      (footprint "eagle-import:5V-LM3150MH_0603")
      (fields (field (name "MANUFACTURER_PART_NUMBER") "CGA3E2X7R1H104K080AA"))
      (libsource (lib "eagle-import") (part "5V-LM3150MH_CGA3E2X7R1H104K080AA"))
    )
    (comp (ref "C24")
      (value "15nF")
      (footprint "eagle-import:CGA4F2C0G1H153J085AA_CAPC2012X100N")
      (fields
        (field (name "MANUFACTURER_PART_NUMBER") "CGA4F2C0G1H153J085AA")
        (field (name "MOUSER_PART_NUMBER") "810-CGA4F2C0G1H153J")
        (field (name "RS_PART_NUMBER") "9155168")
      )
      (libsource (lib "eagle-import") (part "CGA4F2C0G1H153J085AA_CGA4F2C0G1H153J085AA"))
    )
    (comp (ref "C25")
      (value "2.2uF")
      (footprint "eagle-import:5V-LM3150MH_0805")
      (fields (field (name "MANUFACTURER_PART_NUMBER") "EMK212BJ225KGT"))
      (libsource (lib "eagle-import") (part "5V-LM3150MH_EMK212BJ225KG-T"))
    )
    (comp (ref "C26")
      (value "470nF")
      (footprint "eagle-import:5V-LM3150MH_1206")
      (fields (field (name "MANUFACTURER_PART_NUMBER") "ECPU1C474MA5"))
      (libsource (lib "eagle-import") (part "5V-LM3150MH_ECPU1C474MA5"))
    )
    (comp (ref "C27")
      (value "62pF")
      (footprint "eagle-import:5V-LM3150MH_0805")
      (fields (field (name "MANUFACTURER_PART_NUMBER") "CL21C620JBANNNC"))
      (libsource (lib "eagle-import") (part "5V-LM3150MH_CL21C620JBANNNC"))
    )
    (comp (ref "C28")
      (value "EEF-CX0J151XR")
      (footprint "eagle-import:5V-LM3150MH_C2917")
      (libsource (lib "eagle-import") (part "5V-LM3150MH_CUSTOM_CAP"))
    )
    (comp (ref "L2")
      (value "2.2uH")
      (footprint "eagle-import:5V-LM3150MH_XAL5030")
      (fields (field (name "MANUFACTURER_PART_NUMBER") "XAL5030222MEB"))
      (libsource (lib "eagle-import") (part "5V-LM3150MH_XAL5030-222MEB"))
    )
    (comp (ref "L4")
      (value "3.9uH")
      (footprint "eagle-import:5V-LM3150MH_IND_NPI43C")
      (fields (field (name "MANUFACTURER_PART_NUMBER") "NPI43C3R9MTRF"))
      (libsource (lib "eagle-import") (part "5V-LM3150MH_NPI43C3R9MTRF"))
    )
    (comp (ref "M3")
      (value "30V")
      (footprint "eagle-import:5V-LM3150MH_TRANS_NEXFET_Q5A")
      (fields (field (name "MANUFACTURER_PART_NUMBER") "CSD17579Q5A"))
      (libsource (lib "eagle-import") (part "5V-LM3150MH_CSD17579Q5A"))
    )
    (comp (ref "M4")
      (value "60V")
      (footprint "eagle-import:5V-LM3150MH_TRANS_NEXFET_Q5A")
      (fields (field (name "MANUFACTURER_PART_NUMBER") "CSD18537NQ5A"))
      (libsource (lib "eagle-import") (part "5V-LM3150MH_CSD18537NQ5A"))
    )
    (comp (ref "R6")
      (value "100m")
      (footprint "eagle-import:5V-LM3150MH_0603")
      (fields
        (field (name "MANUFACTURER_PART_NUMBER") "ERJ3RSFR10V")
        (field (name "POWER") "0.1")
        (field (name "TOLERANCE") "1.0")
      )
      (libsource (lib "eagle-import") (part "5V-LM3150MH_ERJ-3RSFR10V"))
    )
    (comp (ref "R7")
      (value "51.1k")
      (footprint "eagle-import:5V-LM3150MH_0805")
      (fields
        (field (name "MANUFACTURER_PART_NUMBER") "ERJ6ENF5112V")
        (field (name "POWER") "0.125")
        (field (name "TOLERANCE") "1.0")
      )
      (libsource (lib "eagle-import") (part "5V-LM3150MH_ERJ-6ENF5112V"))
    )
    (comp (ref "R8")
      (value "1.58k")
      (footprint "eagle-import:5V-LM3150MH_0805")
      (fields
        (field (name "MANUFACTURER_PART_NUMBER") "ERJ6ENF1581V")
        (field (name "POWER") "0.125")
        (field (name "TOLERANCE") "1.0")
      )
      (libsource (lib "eagle-import") (part "5V-LM3150MH_ERJ-6ENF1581V"))
    )
    (comp (ref "R9")
      (value "73.2k")
      (footprint "eagle-import:5V-LM3150MH_0805")
      (fields
        (field (name "MANUFACTURER_PART_NUMBER") "CRCW080573K2FKEA")
        (field (name "POWER") "0.125")
        (field (name "TOLERANCE") "1.0")
      )
      (libsource (lib "eagle-import") (part "5V-LM3150MH_CRCW080573K2FKEA"))
    )
    (comp (ref "R10")
      (value "10k")
      (footprint "eagle-import:5V-LM3150MH_0805")
      (fields
        (field (name "MANUFACTURER_PART_NUMBER") "CRCW080510K0FKEA")
        (field (name "POWER") "0.125")
        (field (name "TOLERANCE") "1.0")
      )
      (libsource (lib "eagle-import") (part "5V-LM3150MH_CRCW080510K0FKEA"))
    )
    (comp (ref "U2")
      (value "5V-LM3150MH_LM3150MH/NOPB")
      (footprint "eagle-import:5V-LM3150MH_MXA14A")
      (fields (field (name "MANUFACTURER_PART_NUMBER") "LM3150MHNOPB"))
      (libsource (lib "eagle-import") (part "5V-LM3150MH_LM3150MH/NOPB"))
    )
  )
  (nets
    (net (code "1") (name "5V") (class "Default")
      (node (ref "C27") (pin "1") (pinfunction "1_1") (pintype "passive"))
      (node (ref "C28") (pin "P$1") (pinfunction "+_P$1") (pintype "passive"))
      (node (ref "C39") (pin "2") (pinfunction "P$2_2") (pintype "passive"))
      (node (ref "J5") (pin "1") (pinfunction "1_1") (pintype "passive"))
      (node (ref "J6") (pin "1") (pinfunction "1_1") (pintype "passive"))
      (node (ref "JP1") (pin "1") (pinfunction "1_1") (pintype "passive"))
      (node (ref "JP1") (pin "3") (pinfunction "3_3") (pintype "passive"))
      (node (ref "L2") (pin "2") (pinfunction "2_2") (pintype "passive"))
      (node (ref "R19") (pin "1") (pinfunction "1_1") (pintype "passive"))
      (node (ref "R23") (pin "1") (pinfunction "1_1") (pintype "passive"))
      (node (ref "R24") (pin "1") (pinfunction "1_1") (pintype "passive"))
      (node (ref "R9") (pin "1") (pinfunction "1_1") (pintype "passive"))
      (node (ref "U4") (pin "8") (pinfunction "VDD_8") (pintype "bidirectional"))
    )
    (net (code "2") (name "5V_ALWAYS_ON") (class "Default")
      (node (ref "C37") (pin "1") (pinfunction "1_1") (pintype "passive"))
      (node (ref "J3") (pin "2") (pinfunction "2_2") (pintype "passive"))
      (node (ref "R30") (pin "2") (pinfunction "2_2") (pintype "passive"))
      (node (ref "R39") (pin "2") (pinfunction "2_2") (pintype "passive"))
      (node (ref "R40") (pin "2") (pinfunction "2_2") (pintype "passive"))
      (node (ref "R41") (pin "2") (pinfunction "2_2") (pintype "passive"))
      (node (ref "U10") (pin "VCC") (pinfunction "VCC_VCC") (pintype "bidirectional"))
      (node (ref "U11") (pin "VCC") (pinfunction "VCC_VCC") (pintype "bidirectional"))
      (node (ref "U13") (pin "2") (pinfunction "VOUT_2") (pintype "output"))
      (node (ref "U14") (pin "VCC") (pinfunction "VCC_VCC") (pintype "bidirectional"))
      (node (ref "U9") (pin "VCC") (pinfunction "VCC_VCC") (pintype "bidirectional"))
    )
    (net (code "3") (name "BATT_IN") (class "Default")
      (node (ref "CON7") (pin "+") (pinfunction "+_+") (pintype "power_in"))
      (node (ref "CR2") (pin "1") (pinfunction "1_1") (pintype "passive"))
      (node (ref "Q2") (pin "1") (pinfunction "S_1") (pintype "bidirectional"))
      (node (ref "Q2") (pin "2") (pinfunction "S_2") (pintype "bidirectional"))
      (node (ref "Q2") (pin "3") (pinfunction "S_3") (pintype "bidirectional"))
      (node (ref "Q7") (pin "3") (pinfunction "S_3") (pintype "bidirectional"))
      (node (ref "Q8") (pin "3") (pinfunction "S_3") (pintype "bidirectional"))
      (node (ref "Q9") (pin "3") (pinfunction "S_3") (pintype "bidirectional"))
      (node (ref "R20") (pin "2") (pinfunction "2_2") (pintype "passive"))
      (node (ref "R28") (pin "1") (pinfunction "1_1") (pintype "passive"))
      (node (ref "R33") (pin "1") (pinfunction "1_1") (pintype "passive"))
      (node (ref "U8") (pin "1") (pinfunction "IN_1") (pintype "input"))
    )
    (net (code "4") (name "BATT_SENSE") (class "Default")
      (node (ref "R32") (pin "1") (pinfunction "1_1") (pintype "passive"))
      (node (ref "R33") (pin "2") (pinfunction "2_2") (pintype "passive"))
      (node (ref "U4") (pin "4") (pinfunction "AIN0_4") (pintype "bidirectional"))
    )
    (net (code "5") (name "CHASSIS") (class "Default")
      (node (ref "JP2") (pin "1") (pinfunction "1_1") (pintype "passive"))
    )
    (net (code "6") (name "GND") (class "Default")
      (node (ref "C1") (pin "2") (pinfunction "2_2") (pintype "passive"))
      (node (ref "C10") (pin "2") (pinfunction "2_2") (pintype "passive"))
      (node (ref "C11") (pin "2") (pinfunction "2_2") (pintype "passive"))
      (node (ref "C12") (pin "2") (pinfunction "2_2") (pintype "bidirectional"))
      (node (ref "C13") (pin "2") (pinfunction "2_2") (pintype "passive"))
      (node (ref "C16") (pin "P$3") (pinfunction "-_P$3") (pintype "passive"))
      (node (ref "C17") (pin "2") (pinfunction "2_2") (pintype "passive"))
      (node (ref "C18") (pin "2") (pinfunction "2_2") (pintype "passive"))
      (node (ref "C19") (pin "2") (pinfunction "2_2") (pintype "passive"))
      (node (ref "C2") (pin "2") (pinfunction "2_2") (pintype "passive"))
      (node (ref "C20") (pin "2") (pinfunction "-_2") (pintype "passive"))
      (node (ref "C21") (pin "2") (pinfunction "2_2") (pintype "passive"))
      (node (ref "C22") (pin "2") (pinfunction "2_2") (pintype "passive"))
      (node (ref "C23") (pin "2") (pinfunction "2_2") (pintype "passive"))
      (node (ref "C24") (pin "2") (pinfunction "2_2") (pintype "bidirectional"))
      (node (ref "C25") (pin "2") (pinfunction "2_2") (pintype "passive"))
      (node (ref "C28") (pin "P$2") (pinfunction "-_P$2") (pintype "passive"))
      (node (ref "C29") (pin "2") (pinfunction "2_2") (pintype "passive"))
      (node (ref "C31") (pin "2") (pinfunction "-_2") (pintype "bidirectional"))
      (node (ref "C32") (pin "2") (pinfunction "-_2") (pintype "bidirectional"))
      (node (ref "C33") (pin "2") (pinfunction "-_2") (pintype "bidirectional"))
      (node (ref "C34") (pin "2") (pinfunction "-_2") (pintype "bidirectional"))
      (node (ref "C35") (pin "2") (pinfunction "-_2") (pintype "bidirectional"))
      (node (ref "C36") (pin "2") (pinfunction "2_2") (pintype "passive"))
      (node (ref "C37") (pin "2") (pinfunction "2_2") (pintype "passive"))
      (node (ref "C38") (pin "2") (pinfunction "2_2") (pintype "passive"))
      (node (ref "C39") (pin "1") (pinfunction "P$1_1") (pintype "passive"))
      (node (ref "C4") (pin "2") (pinfunction "2_2") (pintype "passive"))
      (node (ref "C40") (pin "2") (pinfunction "2_2") (pintype "passive"))
      (node (ref "C41") (pin "2") (pinfunction "2_2") (pintype "passive"))
      (node (ref "C5") (pin "2") (pinfunction "2_2") (pintype "passive"))
      (node (ref "C6") (pin "2") (pinfunction "2_2") (pintype "passive"))
      (node (ref "C7") (pin "2") (pinfunction "-_2") (pintype "passive"))
      (node (ref "C8") (pin "2") (pinfunction "-_2") (pintype "passive"))
      (node (ref "C9") (pin "2") (pinfunction "2_2") (pintype "passive"))
      (node (ref "CON1") (pin "-") (pinfunction "-_-") (pintype "power_in"))
      (node (ref "CON2") (pin "-") (pinfunction "-_-") (pintype "power_in"))
      (node (ref "CON3") (pin "-") (pinfunction "-_-") (pintype "power_in"))
      (node (ref "CON4") (pin "-") (pinfunction "-_-") (pintype "power_in"))
      (node (ref "CON7") (pin "-") (pinfunction "-_-") (pintype "power_in"))
      (node (ref "CR1") (pin "2") (pinfunction "2_2") (pintype "passive"))
      (node (ref "CR2") (pin "2") (pinfunction "2_2") (pintype "passive"))
      (node (ref "J1") (pin "2") (pinfunction "2_2") (pintype "passive"))
      (node (ref "J1") (pin "3") (pinfunction "3_3") (pintype "passive"))
      (node (ref "J4") (pin "2") (pinfunction "2_2") (pintype "passive"))
      (node (ref "J5") (pin "2") (pinfunction "2_2") (pintype "passive"))
      (node (ref "J6") (pin "2") (pinfunction "2_2") (pintype "passive"))
      (node (ref "J7") (pin "2") (pinfunction "2_2") (pintype "passive"))
      (node (ref "JP1") (pin "10") (pinfunction "10_10") (pintype "passive"))
      (node (ref "JP1") (pin "12") (pinfunction "12_12") (pintype "passive"))
      (node (ref "JP1") (pin "2") (pinfunction "2_2") (pintype "passive"))
      (node (ref "JP1") (pin "4") (pinfunction "4_4") (pintype "passive"))
      (node (ref "JP1") (pin "6") (pinfunction "6_6") (pintype "passive"))
      (node (ref "JP1") (pin "8") (pinfunction "8_8") (pintype "passive"))
      (node (ref "JP2") (pin "2") (pinfunction "2_2") (pintype "passive"))
      (node (ref "LED1") (pin "C") (pinfunction "C_C") (pintype "passive"))
      (node (ref "LED2") (pin "C") (pinfunction "C_C") (pintype "passive"))
      (node (ref "LED3") (pin "C") (pinfunction "C_C") (pintype "passive"))
      (node (ref "LED4") (pin "C") (pinfunction "C_C") (pintype "passive"))
      (node (ref "M2") (pin "1") (pinfunction "SOURCE_1") (pintype "passive"))
      (node (ref "M2") (pin "2") (pinfunction "SOURCE_2") (pintype "passive"))
      (node (ref "M2") (pin "3") (pinfunction "SOURCE_3") (pintype "passive"))
      (node (ref "M4") (pin "1") (pinfunction "SOURCE_1") (pintype "passive"))
      (node (ref "M4") (pin "2") (pinfunction "SOURCE_2") (pintype "passive"))
      (node (ref "M4") (pin "3") (pinfunction "SOURCE_3") (pintype "passive"))
      (node (ref "R10") (pin "2") (pinfunction "2_2") (pintype "passive"))
      (node (ref "R12") (pin "2") (pinfunction "2_2") (pintype "passive"))
      (node (ref "R16") (pin "2") (pinfunction "2_2") (pintype "passive"))
      (node (ref "R17") (pin "2") (pinfunction "2_2") (pintype "passive"))
      (node (ref "R18") (pin "2") (pinfunction "2_2") (pintype "passive"))
      (node (ref "R31") (pin "2") (pinfunction "2_2") (pintype "passive"))
      (node (ref "R32") (pin "2") (pinfunction "2_2") (pintype "passive"))
      (node (ref "R34") (pin "2") (pinfunction "2_2") (pintype "passive"))
      (node (ref "R37") (pin "2") (pinfunction "2_2") (pintype "passive"))
      (node (ref "R38") (pin "1") (pinfunction "1_1") (pintype "passive"))
      (node (ref "R4") (pin "2") (pinfunction "2_2") (pintype "passive"))
      (node (ref "R42") (pin "1") (pinfunction "1_1") (pintype "passive"))
      (node (ref "U1") (pin "14") (pinfunction "PGND_2_14") (pintype "passive"))
      (node (ref "U1") (pin "15") (pinfunction "SGND_15") (pintype "passive"))
      (node (ref "U1") (pin "5") (pinfunction "SGND_2_5") (pintype "passive"))
      (node (ref "U1") (pin "9") (pinfunction "SGND_9") (pintype "passive"))
      (node (ref "U10") (pin "GND") (pinfunction "GND_GND") (pintype "bidirectional"))
      (node (ref "U10") (pin "GND@1") (pinfunction "GND_GND@1") (pintype "bidirectional"))
      (node (ref "U10") (pin "GND@2") (pinfunction "GND_GND@2") (pintype "bidirectional"))
      (node (ref "U11") (pin "GND") (pinfunction "GND_GND") (pintype "bidirectional"))
      (node (ref "U11") (pin "GND@1") (pinfunction "GND_GND@1") (pintype "bidirectional"))
      (node (ref "U11") (pin "GND@2") (pinfunction "GND_GND@2") (pintype "bidirectional"))
      (node (ref "U13") (pin "1") (pinfunction "GND_1") (pintype "passive"))
      (node (ref "U14") (pin "GND") (pinfunction "GND_GND") (pintype "bidirectional"))
      (node (ref "U14") (pin "GND@1") (pinfunction "GND_GND@1") (pintype "bidirectional"))
      (node (ref "U14") (pin "GND@2") (pinfunction "GND_GND@2") (pintype "bidirectional"))
      (node (ref "U2") (pin "14") (pinfunction "PGND_2_14") (pintype "passive"))
      (node (ref "U2") (pin "15") (pinfunction "SGND_15") (pintype "passive"))
      (node (ref "U2") (pin "5") (pinfunction "SGND_2_5") (pintype "passive"))
      (node (ref "U2") (pin "9") (pinfunction "SGND_9") (pintype "passive"))
      (node (ref "U3") (pin "5") (pinfunction "GND_5") (pintype "power_in"))
      (node (ref "U4") (pin "1") (pinfunction "ADDR_1") (pintype "bidirectional"))
      (node (ref "U4") (pin "3") (pinfunction "GND_3") (pintype "bidirectional"))
      (node (ref "U6") (pin "2") (pinfunction "S_2") (pintype "passive"))
      (node (ref "U7") (pin "2") (pinfunction "S_2") (pintype "passive"))
      (node (ref "U8") (pin "5") (pinfunction "GND_5") (pintype "power_in"))
      (node (ref "U9") (pin "GND") (pinfunction "GND_GND") (pintype "bidirectional"))
      (node (ref "U9") (pin "GND@1") (pinfunction "GND_GND@1") (pintype "bidirectional"))
      (node (ref "U9") (pin "GND@2") (pinfunction "GND_GND@2") (pintype "bidirectional"))
    )
    (net (code "7") (name "MOTOR_PULLUP") (class "Default")
      (node (ref "J9") (pin "1") (pinfunction "1_1") (pintype "passive"))
      (node (ref "R13") (pin "2") (pinfunction "2_2") (pintype "passive"))
    )
    (net (code "8") (name "MOTOR_V+") (class "Default")
      (node (ref "C3") (pin "1") (pinfunction "1_1") (pintype "passive"))
      (node (ref "C31") (pin "1") (pinfunction "+_1") (pintype "bidirectional"))
      (node (ref "C32") (pin "1") (pinfunction "+_1") (pintype "bidirectional"))
      (node (ref "C33") (pin "1") (pinfunction "+_1") (pintype "bidirectional"))
      (node (ref "C34") (pin "1") (pinfunction "+_1") (pintype "bidirectional"))
      (node (ref "C35") (pin "1") (pinfunction "+_1") (pintype "bidirectional"))
      (node (ref "CON1") (pin "+") (pinfunction "+_+") (pintype "power_in"))
      (node (ref "CON2") (pin "+") (pinfunction "+_+") (pintype "power_in"))
      (node (ref "CON3") (pin "+") (pinfunction "+_+") (pintype "power_in"))
      (node (ref "CON4") (pin "+") (pinfunction "+_+") (pintype "power_in"))
      (node (ref "Q7") (pin "4") (pinfunction "D_4") (pintype "bidirectional"))
      (node (ref "Q8") (pin "4") (pinfunction "D_4") (pintype "bidirectional"))
      (node (ref "Q9") (pin "4") (pinfunction "D_4") (pintype "bidirectional"))
      (node (ref "R29") (pin "1") (pinfunction "1_1") (pintype "passive"))
      (node (ref "R36") (pin "1") (pinfunction "1_1") (pintype "passive"))
    )
    (net (code "9") (name "M_N_GATE") (class "Default")
      (node (ref "R12") (pin "1") (pinfunction "1_1") (pintype "passive"))
      (node (ref "R13") (pin "1") (pinfunction "1_1") (pintype "passive"))
      (node (ref "U11") (pin "OUT") (pinfunction "OUT_OUT") (pintype "bidirectional"))
      (node (ref "U7") (pin "1") (pinfunction "G_1") (pintype "passive"))
    )
    (net (code "10") (name "Net-(C7-+)") (class "Default")
      (node (ref "C7") (pin "1") (pinfunction "+_1") (pintype "passive"))
      (node (ref "C8") (pin "1") (pinfunction "+_1") (pintype "passive"))
      (node (ref "R1") (pin "2") (pinfunction "2_2") (pintype "passive"))
    )
    (net (code "11") (name "Net-(C20-+)") (class "Default")
      (node (ref "C20") (pin "1") (pinfunction "+_1") (pintype "passive"))
      (node (ref "R6") (pin "2") (pinfunction "2_2") (pintype "passive"))
    )
    (net (code "12") (name "Net-(J2-Pad1)") (class "Default")
      (node (ref "J2") (pin "1") (pinfunction "1_1") (pintype "passive"))
      (node (ref "J9") (pin "2") (pinfunction "2_2") (pintype "passive"))
    )
    (net (code "13") (name "Net-(J3-Pad1)") (class "Default")
      (node (ref "J3") (pin "1") (pinfunction "1_1") (pintype "passive"))
      (node (ref "J8") (pin "2") (pinfunction "2_2") (pintype "passive"))
    )
    (net (code "14") (name "Net-(LED1-PadA)") (class "Default")
      (node (ref "LED1") (pin "A") (pinfunction "A_A") (pintype "passive"))
      (node (ref "R19") (pin "2") (pinfunction "2_2") (pintype "passive"))
    )
    (net (code "15") (name "Net-(LED2-PadA)") (class "Default")
      (node (ref "LED2") (pin "A") (pinfunction "A_A") (pintype "passive"))
      (node (ref "R22") (pin "2") (pinfunction "2_2") (pintype "passive"))
    )
    (net (code "16") (name "Net-(LED3-PadA)") (class "Default")
      (node (ref "LED3") (pin "A") (pinfunction "A_A") (pintype "passive"))
      (node (ref "R25") (pin "2") (pinfunction "2_2") (pintype "passive"))
    )
    (net (code "17") (name "Net-(LED4-PadA)") (class "Default")
      (node (ref "LED4") (pin "A") (pinfunction "A_A") (pintype "passive"))
      (node (ref "R29") (pin "2") (pinfunction "2_2") (pintype "passive"))
    )
    (net (code "18") (name "Net-(M1-GATE)") (class "Default")
      (node (ref "M1") (pin "4") (pinfunction "GATE_4") (pintype "passive"))
      (node (ref "U1") (pin "11") (pinfunction "HG_11") (pintype "passive"))
    )
    (net (code "19") (name "Net-(M2-GATE)") (class "Default")
      (node (ref "M2") (pin "4") (pinfunction "GATE_4") (pintype "passive"))
      (node (ref "U1") (pin "13") (pinfunction "LG_13") (pintype "passive"))
    )
    (net (code "20") (name "Net-(M3-GATE)") (class "Default")
      (node (ref "M3") (pin "4") (pinfunction "GATE_4") (pintype "passive"))
      (node (ref "U2") (pin "11") (pinfunction "HG_11") (pintype "passive"))
    )
    (net (code "21") (name "Net-(M4-GATE)") (class "Default")
      (node (ref "M4") (pin "4") (pinfunction "GATE_4") (pintype "passive"))
      (node (ref "U2") (pin "13") (pinfunction "LG_13") (pintype "passive"))
    )
    (net (code "22") (name "Net-(Q1-G)") (class "Default")
      (node (ref "Q1") (pin "4") (pinfunction "G_4") (pintype "bidirectional"))
      (node (ref "U3") (pin "4") (pinfunction "GATE_4") (pintype "output"))
    )
    (net (code "23") (name "Net-(Q2-G)") (class "Default")
      (node (ref "Q2") (pin "4") (pinfunction "G_4") (pintype "bidirectional"))
      (node (ref "U8") (pin "4") (pinfunction "GATE_4") (pintype "output"))
    )
    (net (code "24") (name "Net-(R4-1)") (class "Default")
      (node (ref "C15") (pin "2") (pinfunction "2_2") (pintype "passive"))
      (node (ref "R11") (pin "1") (pinfunction "1_1") (pintype "passive"))
      (node (ref "R4") (pin "3") (pinfunction "1_3") (pintype "passive"))
      (node (ref "U1") (pin "4") (pinfunction "FB_4") (pintype "passive"))
    )
    (net (code "25") (name "Net-(R17-1)") (class "Default")
      (node (ref "R17") (pin "3") (pinfunction "1_3") (pintype "passive"))
      (node (ref "R20") (pin "1") (pinfunction "1_1") (pintype "passive"))
      (node (ref "U10") (pin "SENSE") (pinfunction "SENSE_SENSE") (pintype "bidirectional"))
    )
    (net (code "26") (name "Net-(R18-1)") (class "Default")
      (node (ref "R18") (pin "3") (pinfunction "1_3") (pintype "passive"))
      (node (ref "R21") (pin "1") (pinfunction "1_1") (pintype "passive"))
      (node (ref "U9") (pin "SENSE") (pinfunction "SENSE_SENSE") (pintype "bidirectional"))
    )
    (net (code "27") (name "Net-(U1-BST)") (class "Default")
      (node (ref "C14") (pin "1") (pinfunction "1_1") (pintype "passive"))
      (node (ref "U1") (pin "12") (pinfunction "BST_12") (pintype "passive"))
    )
    (net (code "28") (name "Net-(U1-ILIM)") (class "Default")
      (node (ref "R3") (pin "2") (pinfunction "2_2") (pintype "passive"))
      (node (ref "U1") (pin "8") (pinfunction "ILIM_8") (pintype "passive"))
    )
    (net (code "29") (name "Net-(U1-RON)") (class "Default")
      (node (ref "R2") (pin "2") (pinfunction "2_2") (pintype "passive"))
      (node (ref "U1") (pin "7") (pinfunction "RON_7") (pintype "passive"))
    )
    (net (code "30") (name "Net-(U1-SS)") (class "Default")
      (node (ref "C12") (pin "1") (pinfunction "1_1") (pintype "bidirectional"))
      (node (ref "U1") (pin "6") (pinfunction "SS_6") (pintype "passive"))
    )
    (net (code "31") (name "Net-(U1-VCC)") (class "Default")
      (node (ref "C13") (pin "1") (pinfunction "1_1") (pintype "passive"))
      (node (ref "U1") (pin "1") (pinfunction "VCC_1") (pintype "passive"))
    )
    (net (code "32") (name "Net-(U2-BST)") (class "Default")
      (node (ref "C26") (pin "1") (pinfunction "1_1") (pintype "passive"))
      (node (ref "U2") (pin "12") (pinfunction "BST_12") (pintype "passive"))
    )
    (net (code "33") (name "Net-(U2-FB)") (class "Default")
      (node (ref "C27") (pin "2") (pinfunction "2_2") (pintype "passive"))
      (node (ref "R10") (pin "1") (pinfunction "1_1") (pintype "passive"))
      (node (ref "R9") (pin "2") (pinfunction "2_2") (pintype "passive"))
      (node (ref "U2") (pin "4") (pinfunction "FB_4") (pintype "passive"))
    )
    (net (code "34") (name "Net-(U2-ILIM)") (class "Default")
      (node (ref "R8") (pin "2") (pinfunction "2_2") (pintype "passive"))
      (node (ref "U2") (pin "8") (pinfunction "ILIM_8") (pintype "passive"))
    )
    (net (code "35") (name "Net-(U2-RON)") (class "Default")
      (node (ref "R7") (pin "2") (pinfunction "2_2") (pintype "passive"))
      (node (ref "U2") (pin "7") (pinfunction "RON_7") (pintype "passive"))
    )
    (net (code "36") (name "Net-(U2-SS)") (class "Default")
      (node (ref "C24") (pin "1") (pinfunction "1_1") (pintype "bidirectional"))
      (node (ref "U2") (pin "6") (pinfunction "SS_6") (pintype "passive"))
    )
    (net (code "37") (name "Net-(U2-VCC)") (class "Default")
      (node (ref "C25") (pin "1") (pinfunction "1_1") (pintype "passive"))
      (node (ref "U2") (pin "1") (pinfunction "VCC_1") (pintype "passive"))
    )
    (net (code "38") (name "Net-(U4-AIN1)") (class "Default")
      (node (ref "R26") (pin "2") (pinfunction "2_2") (pintype "passive"))
      (node (ref "R31") (pin "1") (pinfunction "1_1") (pintype "passive"))
      (node (ref "U4") (pin "5") (pinfunction "AIN1_5") (pintype "bidirectional"))
    )
    (net (code "39") (name "Net-(U4-AIN2)") (class "Default")
      (node (ref "R34") (pin "1") (pinfunction "1_1") (pintype "passive"))
      (node (ref "R35") (pin "2") (pinfunction "2_2") (pintype "passive"))
      (node (ref "U4") (pin "6") (pinfunction "AIN2_6") (pintype "bidirectional"))
    )
    (net (code "40") (name "Net-(U4-AIN3)") (class "Default")
      (node (ref "R36") (pin "2") (pinfunction "2_2") (pintype "passive"))
      (node (ref "R37") (pin "1") (pinfunction "1_1") (pintype "passive"))
      (node (ref "U4") (pin "7") (pinfunction "AIN3_7") (pintype "bidirectional"))
    )
    (net (code "41") (name "Net-(U5-D)") (class "Default")
      (node (ref "R40") (pin "1") (pinfunction "1_1") (pintype "passive"))
      (node (ref "U5") (pin "3") (pinfunction "D_3") (pintype "passive"))
    )
    (net (code "42") (name "Net-(U5-G)") (class "Default")
      (node (ref "R30") (pin "1") (pinfunction "1_1") (pintype "passive"))
      (node (ref "U10") (pin "OUT") (pinfunction "OUT_OUT") (pintype "bidirectional"))
      (node (ref "U5") (pin "1") (pinfunction "G_1") (pintype "passive"))
    )
    (net (code "43") (name "Net-(U5-S)") (class "Default")
      (node (ref "C40") (pin "1") (pinfunction "1_1") (pintype "passive"))
      (node (ref "R38") (pin "2") (pinfunction "2_2") (pintype "passive"))
      (node (ref "U11") (pin "SENSE") (pinfunction "SENSE_SENSE") (pintype "bidirectional"))
      (node (ref "U5") (pin "2") (pinfunction "S_2") (pintype "passive"))
    )
    (net (code "44") (name "Net-(U6-D)") (class "Default")
      (node (ref "R15") (pin "1") (pinfunction "1_1") (pintype "passive"))
      (node (ref "U6") (pin "3") (pinfunction "D_3") (pintype "passive"))
    )
    (net (code "45") (name "Net-(U7-D)") (class "Default")
      (node (ref "R5") (pin "1") (pinfunction "1_1") (pintype "passive"))
      (node (ref "U7") (pin "3") (pinfunction "D_3") (pintype "passive"))
    )
    (net (code "46") (name "Net-(U12-D)") (class "Default")
      (node (ref "R41") (pin "1") (pinfunction "1_1") (pintype "passive"))
      (node (ref "U12") (pin "3") (pinfunction "D_3") (pintype "passive"))
    )
    (net (code "47") (name "Net-(U12-G)") (class "Default")
      (node (ref "R39") (pin "1") (pinfunction "1_1") (pintype "passive"))
      (node (ref "U12") (pin "1") (pinfunction "G_1") (pintype "passive"))
      (node (ref "U9") (pin "OUT") (pinfunction "OUT_OUT") (pintype "bidirectional"))
    )
    (net (code "48") (name "Net-(U12-S)") (class "Default")
      (node (ref "C41") (pin "1") (pinfunction "1_1") (pintype "passive"))
      (node (ref "R42") (pin "2") (pinfunction "2_2") (pintype "passive"))
      (node (ref "U12") (pin "2") (pinfunction "S_2") (pintype "passive"))
      (node (ref "U14") (pin "SENSE") (pinfunction "SENSE_SENSE") (pintype "bidirectional"))
    )
    (net (code "49") (name "PS_IN") (class "Default")
      (node (ref "CR1") (pin "1") (pinfunction "1_1") (pintype "passive"))
      (node (ref "J1") (pin "1") (pinfunction "1_1") (pintype "passive"))
      (node (ref "Q1") (pin "1") (pinfunction "S_1") (pintype "bidirectional"))
      (node (ref "Q1") (pin "2") (pinfunction "S_2") (pintype "bidirectional"))
      (node (ref "Q1") (pin "3") (pinfunction "S_3") (pintype "bidirectional"))
      (node (ref "R26") (pin "1") (pinfunction "1_1") (pintype "passive"))
      (node (ref "U3") (pin "1") (pinfunction "IN_1") (pintype "input"))
    )
    (net (code "50") (name "P_GATES") (class "Default")
      (node (ref "C30") (pin "2") (pinfunction "2_2") (pintype "passive"))
      (node (ref "Q3") (pin "1") (pinfunction "G_1") (pintype "bidirectional"))
      (node (ref "R15") (pin "2") (pinfunction "2_2") (pintype "passive"))
      (node (ref "R27") (pin "2") (pinfunction "2_2") (pintype "passive"))
    )
    (net (code "51") (name "P_GATES_MOTOR") (class "Default")
      (node (ref "C3") (pin "2") (pinfunction "2_2") (pintype "passive"))
      (node (ref "Q7") (pin "1") (pinfunction "G_1") (pintype "bidirectional"))
      (node (ref "Q8") (pin "1") (pinfunction "G_1") (pintype "bidirectional"))
      (node (ref "Q9") (pin "1") (pinfunction "G_1") (pintype "bidirectional"))
      (node (ref "R28") (pin "2") (pinfunction "2_2") (pintype "passive"))
      (node (ref "R5") (pin "2") (pinfunction "2_2") (pintype "passive"))
    )
    (net (code "52") (name "SCL") (class "Default")
      (node (ref "J10") (pin "2") (pinfunction "2_2") (pintype "passive"))
      (node (ref "R23") (pin "2") (pinfunction "2_2") (pintype "passive"))
      (node (ref "U4") (pin "10") (pinfunction "SCL_10") (pintype "bidirectional"))
    )
    (net (code "53") (name "SDA") (class "Default")
      (node (ref "J10") (pin "1") (pinfunction "1_1") (pintype "passive"))
      (node (ref "R24") (pin "2") (pinfunction "2_2") (pintype "passive"))
      (node (ref "U4") (pin "9") (pinfunction "SDA_9") (pintype "bidirectional"))
    )
    (net (code "54") (name "SW1") (class "Default")
      (node (ref "C26") (pin "2") (pinfunction "2_2") (pintype "passive"))
      (node (ref "L2") (pin "1") (pinfunction "1_1") (pintype "passive"))
      (node (ref "M3") (pin "1") (pinfunction "SOURCE_1") (pintype "passive"))
      (node (ref "M3") (pin "2") (pinfunction "SOURCE_2") (pintype "passive"))
      (node (ref "M3") (pin "3") (pinfunction "SOURCE_3") (pintype "passive"))
      (node (ref "M4") (pin "5") (pinfunction "DRAIN_5") (pintype "passive"))
      (node (ref "M4") (pin "6") (pinfunction "DRAIN_6") (pintype "passive"))
      (node (ref "M4") (pin "7") (pinfunction "DRAIN_7") (pintype "passive"))
      (node (ref "M4") (pin "8") (pinfunction "DRAIN_8") (pintype "passive"))
      (node (ref "M4") (pin "9") (pinfunction "DRAIN_9") (pintype "passive"))
      (node (ref "R8") (pin "1") (pinfunction "1_1") (pintype "passive"))
      (node (ref "U2") (pin "10") (pinfunction "SW_10") (pintype "passive"))
    )
    (net (code "55") (name "SW2") (class "Default")
      (node (ref "C14") (pin "2") (pinfunction "2_2") (pintype "passive"))
      (node (ref "L1") (pin "1") (pinfunction "1_1") (pintype "passive"))
      (node (ref "M1") (pin "1") (pinfunction "SOURCE_1") (pintype "passive"))
      (node (ref "M1") (pin "2") (pinfunction "SOURCE_2") (pintype "passive"))
      (node (ref "M1") (pin "3") (pinfunction "SOURCE_3") (pintype "passive"))
      (node (ref "M2") (pin "5") (pinfunction "DRAIN_5") (pintype "passive"))
      (node (ref "M2") (pin "6") (pinfunction "DRAIN_6") (pintype "passive"))
      (node (ref "M2") (pin "7") (pinfunction "DRAIN_7") (pintype "passive"))
      (node (ref "M2") (pin "8") (pinfunction "DRAIN_8") (pintype "passive"))
      (node (ref "M2") (pin "9") (pinfunction "DRAIN_9") (pintype "passive"))
      (node (ref "R3") (pin "1") (pinfunction "1_1") (pintype "passive"))
      (node (ref "U1") (pin "10") (pinfunction "SW_10") (pintype "passive"))
    )
    (net (code "56") (name "SYSTEM_IN") (class "Default")
      (node (ref "C1") (pin "1") (pinfunction "1_1") (pintype "passive"))
      (node (ref "C2") (pin "1") (pinfunction "1_1") (pintype "passive"))
      (node (ref "C29") (pin "1") (pinfunction "1_1") (pintype "passive"))
      (node (ref "C36") (pin "1") (pinfunction "1_1") (pintype "passive"))
      (node (ref "C38") (pin "1") (pinfunction "1_1") (pintype "passive"))
      (node (ref "Q1") (pin "5") (pinfunction "D_5") (pintype "bidirectional"))
      (node (ref "Q1") (pin "6") (pinfunction "D_6") (pintype "bidirectional"))
      (node (ref "Q1") (pin "7") (pinfunction "D_7") (pintype "bidirectional"))
      (node (ref "Q1") (pin "8") (pinfunction "D_8") (pintype "bidirectional"))
      (node (ref "Q1") (pin "9") (pinfunction "D_9") (pintype "bidirectional"))
      (node (ref "Q2") (pin "5") (pinfunction "D_5") (pintype "bidirectional"))
      (node (ref "Q2") (pin "6") (pinfunction "D_6") (pintype "bidirectional"))
      (node (ref "Q2") (pin "7") (pinfunction "D_7") (pintype "bidirectional"))
      (node (ref "Q2") (pin "8") (pinfunction "D_8") (pintype "bidirectional"))
      (node (ref "Q2") (pin "9") (pinfunction "D_9") (pintype "bidirectional"))
      (node (ref "Q3") (pin "3") (pinfunction "S_3") (pintype "bidirectional"))
      (node (ref "R21") (pin "2") (pinfunction "2_2") (pintype "passive"))
      (node (ref "R25") (pin "1") (pinfunction "1_1") (pintype "passive"))
      (node (ref "R27") (pin "1") (pinfunction "1_1") (pintype "passive"))
      (node (ref "U13") (pin "3") (pinfunction "VIN_3") (pintype "power_in"))
      (node (ref "U3") (pin "7") (pinfunction "VDD_7") (pintype "power_in"))
      (node (ref "U3") (pin "8") (pinfunction "OUT_8") (pintype "output"))
      (node (ref "U8") (pin "7") (pinfunction "VDD_7") (pintype "power_in"))
      (node (ref "U8") (pin "8") (pinfunction "OUT_8") (pintype "output"))
    )
    (net (code "57") (name "SYSTEM_PULLUP") (class "Default")
      (node (ref "J2") (pin "2") (pinfunction "2_2") (pintype "passive"))
      (node (ref "J8") (pin "1") (pinfunction "1_1") (pintype "passive"))
      (node (ref "R14") (pin "2") (pinfunction "2_2") (pintype "passive"))
    )
    (net (code "58") (name "SYSTEM_SWITCHED") (class "Default")
      (node (ref "C17") (pin "1") (pinfunction "1_1") (pintype "passive"))
      (node (ref "C18") (pin "1") (pinfunction "1_1") (pintype "passive"))
      (node (ref "C19") (pin "1") (pinfunction "1_1") (pintype "passive"))
      (node (ref "C30") (pin "1") (pinfunction "1_1") (pintype "passive"))
      (node (ref "C4") (pin "1") (pinfunction "1_1") (pintype "passive"))
      (node (ref "C5") (pin "1") (pinfunction "1_1") (pintype "passive"))
      (node (ref "C6") (pin "1") (pinfunction "1_1") (pintype "passive"))
      (node (ref "JP1") (pin "5") (pinfunction "5_5") (pintype "passive"))
      (node (ref "JP1") (pin "7") (pinfunction "7_7") (pintype "passive"))
      (node (ref "L3") (pin "1") (pinfunction "1_1") (pintype "bidirectional"))
      (node (ref "L4") (pin "1") (pinfunction "1_1") (pintype "passive"))
      (node (ref "Q3") (pin "4") (pinfunction "D_4") (pintype "bidirectional"))
    )
    (net (code "59") (name "S_N_GATE") (class "Default")
      (node (ref "R14") (pin "1") (pinfunction "1_1") (pintype "passive"))
      (node (ref "R16") (pin "1") (pinfunction "1_1") (pintype "passive"))
      (node (ref "U14") (pin "OUT") (pinfunction "OUT_OUT") (pintype "bidirectional"))
      (node (ref "U6") (pin "1") (pinfunction "G_1") (pintype "passive"))
    )
    (net (code "60") (name "V_ADJ") (class "Default")
      (node (ref "C15") (pin "1") (pinfunction "1_1") (pintype "passive"))
      (node (ref "C16") (pin "P$1") (pinfunction "+_P$1") (pintype "passive"))
      (node (ref "J4") (pin "1") (pinfunction "1_1") (pintype "passive"))
      (node (ref "J7") (pin "1") (pinfunction "1_1") (pintype "passive"))
      (node (ref "JP1") (pin "11") (pinfunction "11_11") (pintype "passive"))
      (node (ref "JP1") (pin "9") (pinfunction "9_9") (pintype "passive"))
      (node (ref "L1") (pin "2") (pinfunction "2_2") (pintype "passive"))
      (node (ref "R11") (pin "2") (pinfunction "2_2") (pintype "passive"))
      (node (ref "R22") (pin "1") (pinfunction "1_1") (pintype "passive"))
      (node (ref "R35") (pin "1") (pinfunction "1_1") (pintype "passive"))
    )
    (net (code "61") (name "V_BATT_FILTERED_1") (class "Default")
      (node (ref "C21") (pin "1") (pinfunction "1_1") (pintype "passive"))
      (node (ref "C22") (pin "1") (pinfunction "1_1") (pintype "passive"))
      (node (ref "C23") (pin "1") (pinfunction "1_1") (pintype "passive"))
      (node (ref "L4") (pin "2") (pinfunction "2_2") (pintype "passive"))
      (node (ref "M3") (pin "5") (pinfunction "DRAIN_5") (pintype "passive"))
      (node (ref "M3") (pin "6") (pinfunction "DRAIN_6") (pintype "passive"))
      (node (ref "M3") (pin "7") (pinfunction "DRAIN_7") (pintype "passive"))
      (node (ref "M3") (pin "8") (pinfunction "DRAIN_8") (pintype "passive"))
      (node (ref "M3") (pin "9") (pinfunction "DRAIN_9") (pintype "passive"))
      (node (ref "R6") (pin "1") (pinfunction "1_1") (pintype "passive"))
      (node (ref "R7") (pin "1") (pinfunction "1_1") (pintype "passive"))
      (node (ref "U2") (pin "2") (pinfunction "VIN_2") (pintype "passive"))
    )
    (net (code "62") (name "V_BATT_FILTERED_2") (class "Default")
      (node (ref "C10") (pin "1") (pinfunction "1_1") (pintype "passive"))
      (node (ref "C11") (pin "1") (pinfunction "1_1") (pintype "passive"))
      (node (ref "C9") (pin "1") (pinfunction "1_1") (pintype "passive"))
      (node (ref "L3") (pin "2") (pinfunction "2_2") (pintype "bidirectional"))
      (node (ref "M1") (pin "5") (pinfunction "DRAIN_5") (pintype "passive"))
      (node (ref "M1") (pin "6") (pinfunction "DRAIN_6") (pintype "passive"))
      (node (ref "M1") (pin "7") (pinfunction "DRAIN_7") (pintype "passive"))
      (node (ref "M1") (pin "8") (pinfunction "DRAIN_8") (pintype "passive"))
      (node (ref "M1") (pin "9") (pinfunction "DRAIN_9") (pintype "passive"))
      (node (ref "R1") (pin "1") (pinfunction "1_1") (pintype "passive"))
      (node (ref "R2") (pin "1") (pinfunction "1_1") (pintype "passive"))
      (node (ref "U1") (pin "2") (pinfunction "VIN_2") (pintype "passive"))
    )
    (net (code "63") (name "unconnected-(R4-3-Pad1)") (class "Default")
      (node (ref "R4") (pin "1") (pinfunction "3_1") (pintype "passive"))
    )
    (net (code "64") (name "unconnected-(R17-3-Pad1)") (class "Default")
      (node (ref "R17") (pin "1") (pinfunction "3_1") (pintype "passive"))
    )
    (net (code "65") (name "unconnected-(R18-3-Pad1)") (class "Default")
      (node (ref "R18") (pin "1") (pinfunction "3_1") (pintype "passive"))
    )
    (net (code "66") (name "unconnected-(U1-EN-Pad3)") (class "Default")
      (node (ref "U1") (pin "3") (pinfunction "EN_3") (pintype "passive"))
    )
    (net (code "67") (name "unconnected-(U2-EN-Pad3)") (class "Default")
      (node (ref "U2") (pin "3") (pinfunction "EN_3") (pintype "passive"))
    )
    (net (code "68") (name "unconnected-(U4-ALERT-Pad2)") (class "Default")
      (node (ref "U4") (pin "2") (pinfunction "ALERT_2") (pintype "bidirectional"))
    )
  )
)
